# JTAG_-V06.net
KiCad netlist of a schematic drawn in Altium Designer
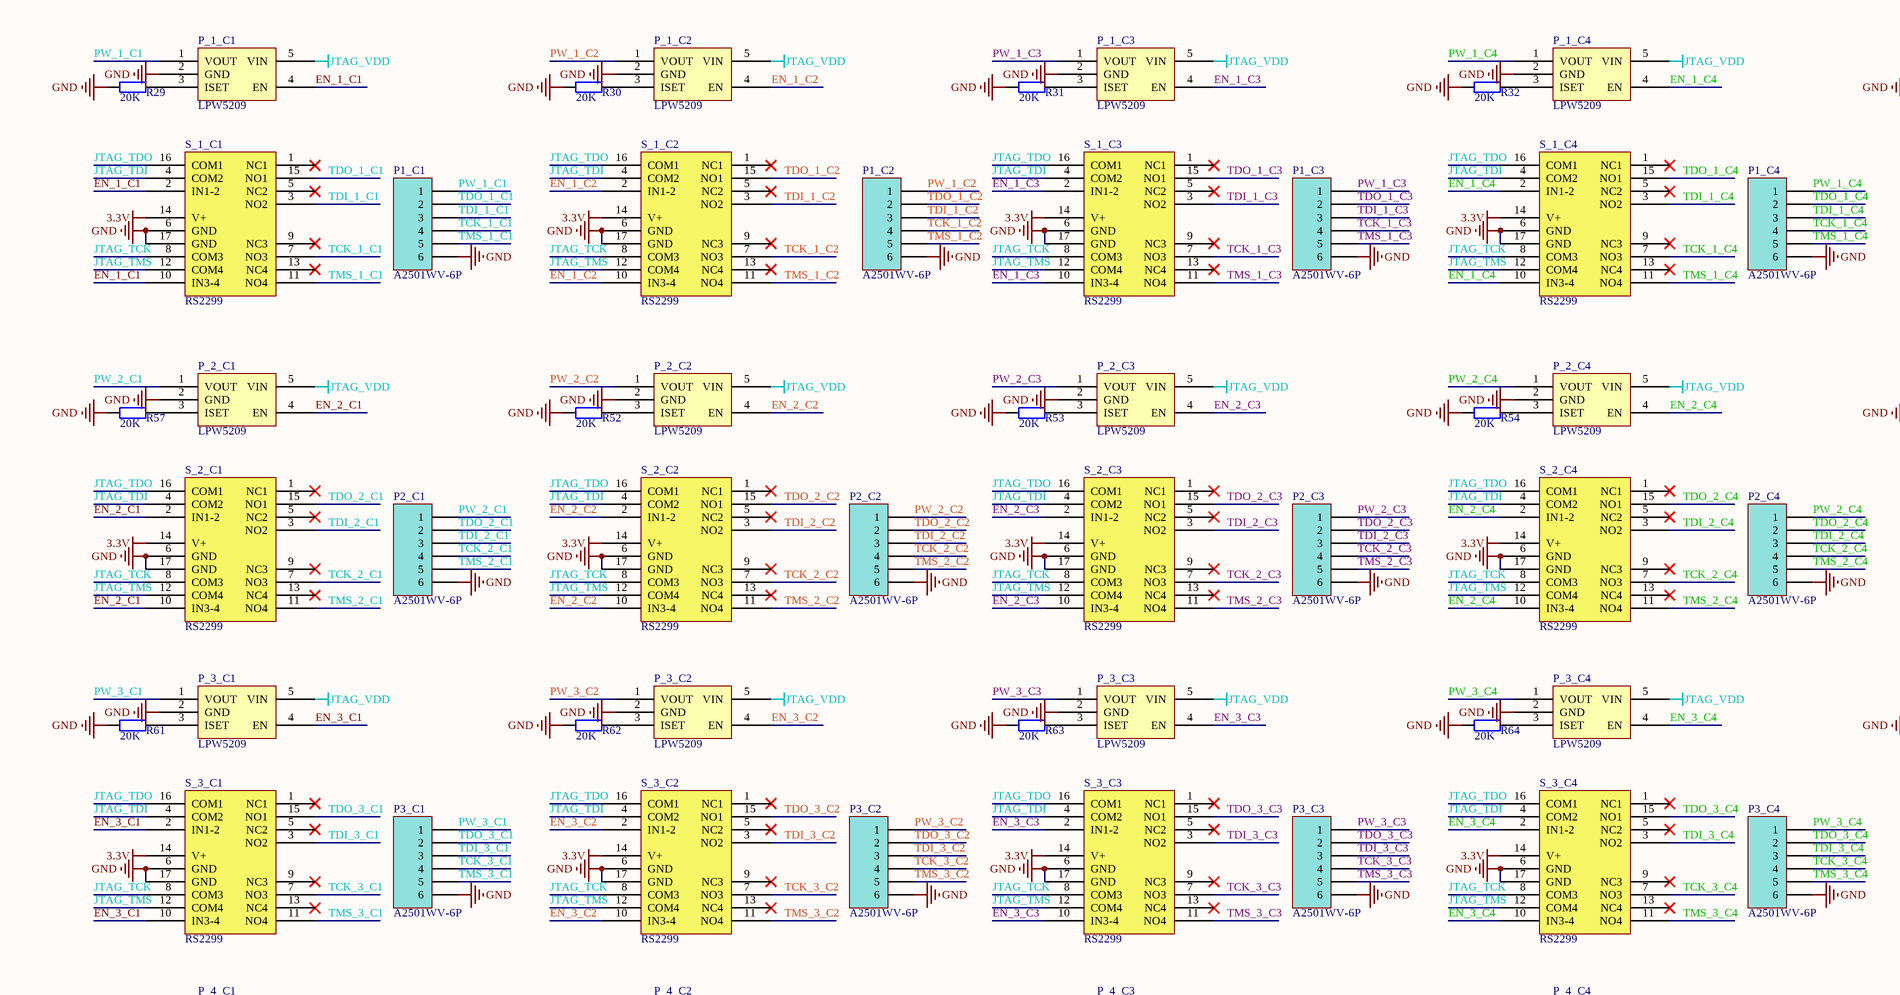
[diagram p0: JTAG批量下载板-V06.SchDoc, top left]
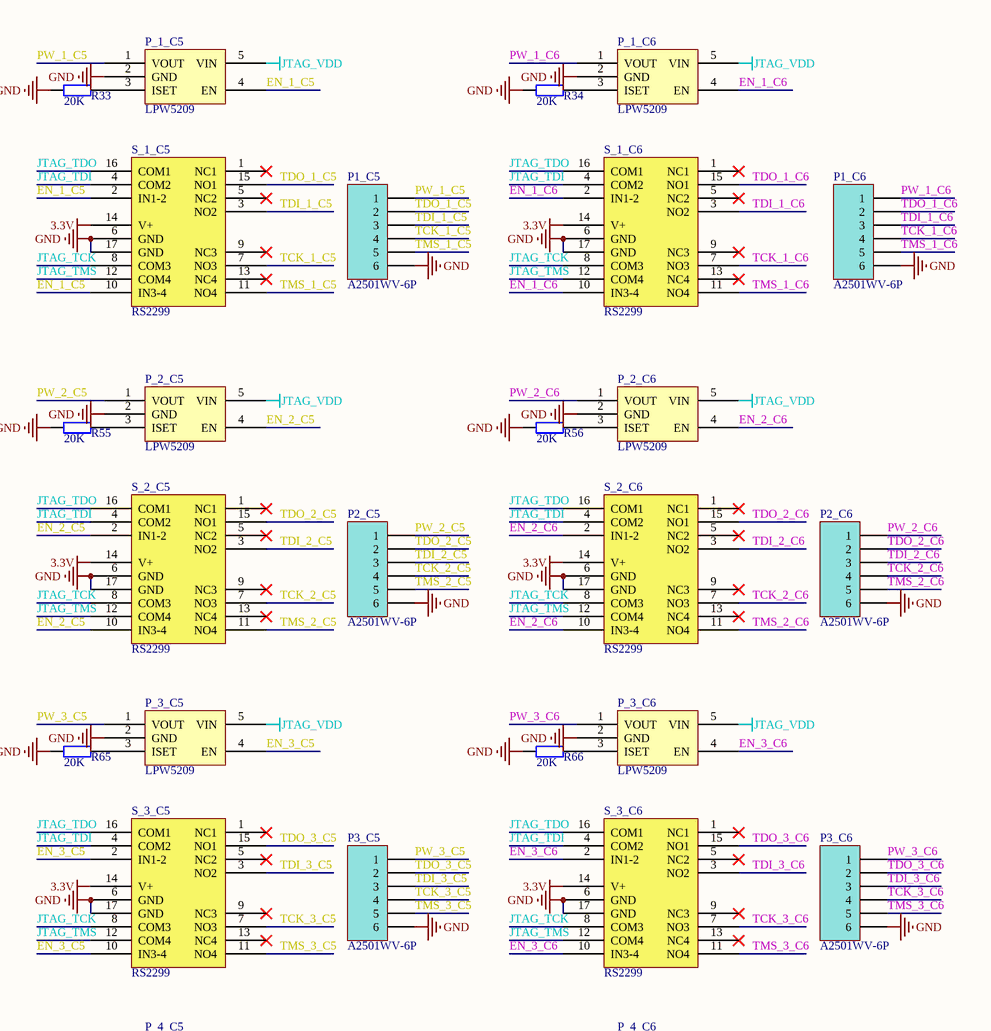
[diagram p1: JTAG批量下载板-V06.SchDoc, top right]
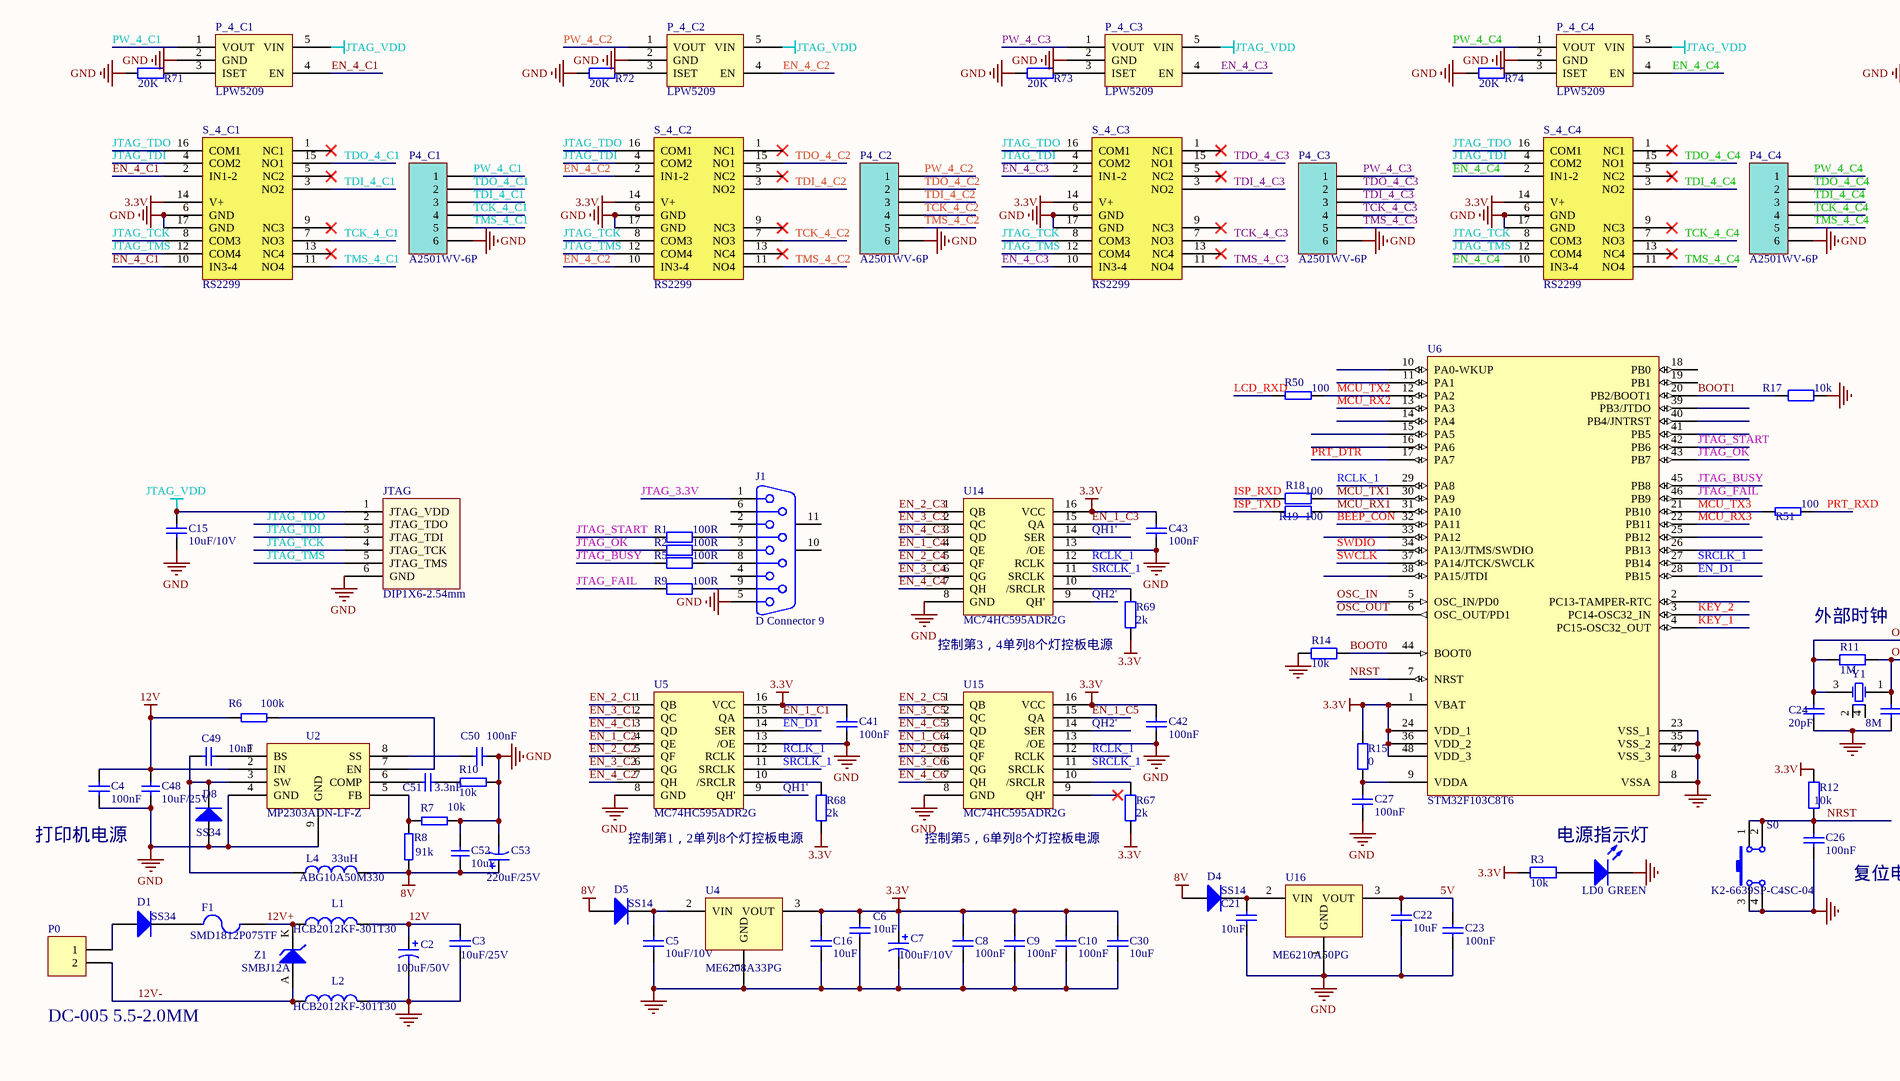
[diagram p2: JTAG批量下载板-V06.SchDoc, bottom left]
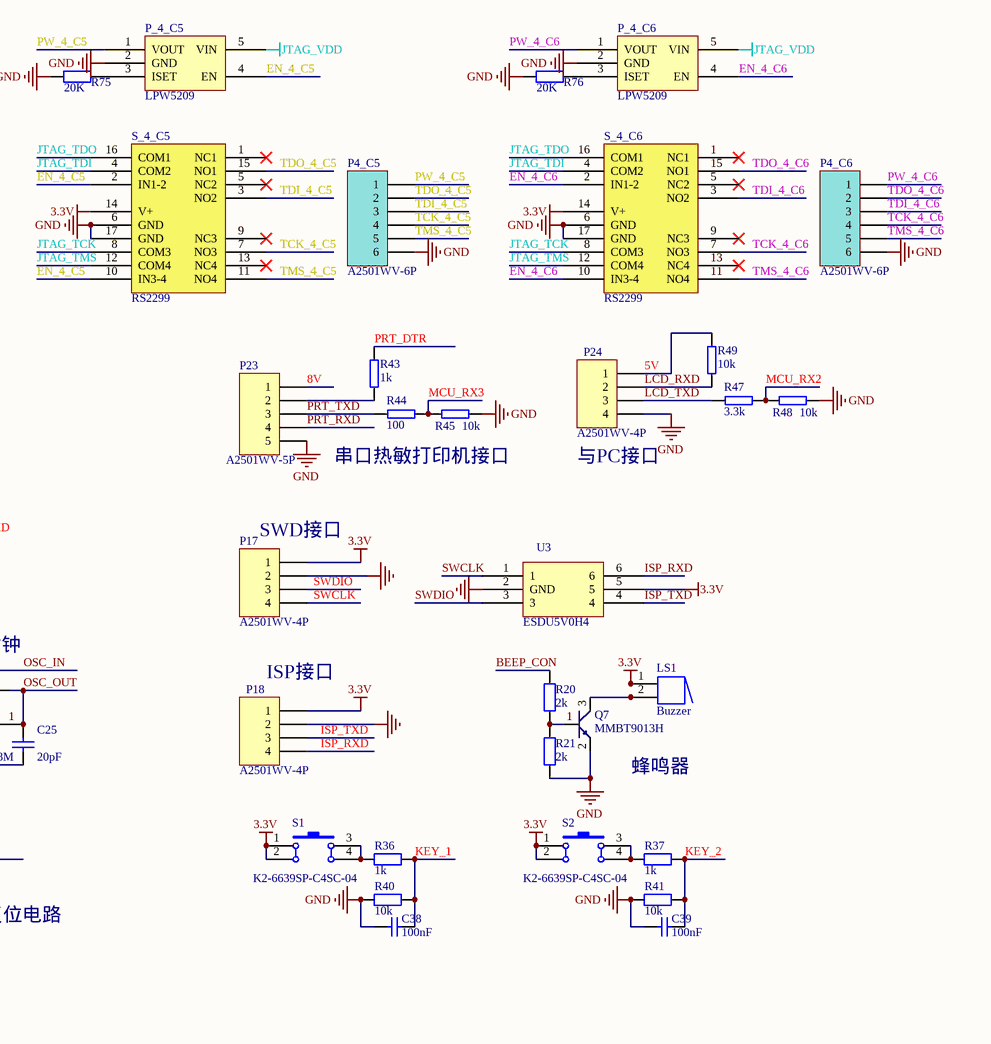
[diagram p3: JTAG批量下载板-V06.SchDoc, bottom right]

(export (version "E")
  (design (tool "Eeschema 10.0.6"))
  (components
    (comp (ref "C2")
      (value "100uF/50V")
      (footprint "RB-6*9")
      (description "Polarized Capacitor (Radial)")
      (fields (field (name "PUBLISHER") "Altium Limited"))
      (libsource (lib "Miscellaneous Devices") (part "Cap Pol1"))
    )
    (comp (ref "C3")
      (value "10uF/25V")
      (footprint "C0805")
      (description "Capacitor")
      (fields (field (name "PUBLISHER") "Altium Limited"))
      (libsource (lib "Miscellaneous Devices") (part "Cap"))
    )
    (comp (ref "C4")
      (value "100nF")
      (footprint "C0603")
      (description "Capacitor")
      (fields (field (name "PUBLISHER") "Altium Limited"))
      (libsource (lib "Miscellaneous Devices") (part "Cap"))
    )
    (comp (ref "C5")
      (value "10uF/10V")
      (footprint "C0603")
      (description "Capacitor")
      (fields (field (name "PUBLISHER") "Altium Limited"))
      (libsource (lib "Miscellaneous Devices") (part "Cap"))
    )
    (comp (ref "C6")
      (value "10uF")
      (footprint "C0603")
      (description "Capacitor")
      (fields (field (name "PUBLISHER") "Altium Limited"))
      (libsource (lib "Miscellaneous Devices") (part "Cap"))
    )
    (comp (ref "C7")
      (value "100uF/10V")
      (footprint "C3528")
      (description "Polarized Capacitor (Radial)")
      (fields (field (name "PUBLISHER") "Altium Limited"))
      (libsource (lib "Miscellaneous Devices") (part "Cap Pol1"))
    )
    (comp (ref "C8")
      (value "100nF")
      (footprint "C0603")
      (description "Capacitor")
      (fields (field (name "PUBLISHER") "Altium Limited"))
      (libsource (lib "Miscellaneous Devices") (part "Cap"))
    )
    (comp (ref "C9")
      (value "100nF")
      (footprint "C0603")
      (description "Capacitor")
      (fields (field (name "PUBLISHER") "Altium Limited"))
      (libsource (lib "Miscellaneous Devices") (part "Cap"))
    )
    (comp (ref "C10")
      (value "100nF")
      (footprint "C0603")
      (description "Capacitor")
      (fields (field (name "PUBLISHER") "Altium Limited"))
      (libsource (lib "Miscellaneous Devices") (part "Cap"))
    )
    (comp (ref "C15")
      (value "10uF/10V")
      (footprint "C0603")
      (description "Capacitor")
      (fields (field (name "PUBLISHER") "Altium Limited"))
      (libsource (lib "Miscellaneous Devices") (part "Cap"))
    )
    (comp (ref "C16")
      (value "10uF")
      (footprint "C0603")
      (description "Capacitor")
      (fields (field (name "PUBLISHER") "Altium Limited"))
      (libsource (lib "Miscellaneous Devices") (part "Cap"))
    )
    (comp (ref "C21")
      (value "10uF")
      (footprint "C0603")
      (description "Capacitor")
      (fields (field (name "PUBLISHER") "Altium Limited"))
      (libsource (lib "Miscellaneous Devices") (part "Cap"))
    )
    (comp (ref "C22")
      (value "10uF")
      (footprint "C0603")
      (description "Capacitor")
      (fields (field (name "PUBLISHER") "Altium Limited"))
      (libsource (lib "Miscellaneous Devices") (part "Cap"))
    )
    (comp (ref "C23")
      (value "100nF")
      (footprint "C0603")
      (description "Capacitor")
      (fields (field (name "PUBLISHER") "Altium Limited"))
      (libsource (lib "Miscellaneous Devices") (part "Cap"))
    )
    (comp (ref "C24")
      (value "20pF")
      (footprint "C0603")
      (description "Capacitor")
      (fields (field (name "PUBLISHER") "Altium Limited"))
      (libsource (lib "Miscellaneous Devices") (part "Cap"))
    )
    (comp (ref "C25")
      (value "20pF")
      (footprint "C0603")
      (description "Capacitor")
      (fields (field (name "PUBLISHER") "Altium Limited"))
      (libsource (lib "Miscellaneous Devices") (part "Cap"))
    )
    (comp (ref "C26")
      (value "100nF")
      (footprint "C0603")
      (description "Capacitor")
      (fields (field (name "PUBLISHER") "Altium Limited"))
      (libsource (lib "Miscellaneous Devices") (part "Cap"))
    )
    (comp (ref "C27")
      (value "100nF")
      (footprint "C0603")
      (description "Capacitor")
      (fields (field (name "PUBLISHER") "Altium Limited"))
      (libsource (lib "Miscellaneous Devices") (part "Cap"))
    )
    (comp (ref "C30")
      (value "10uF")
      (footprint "C0603")
      (description "Capacitor")
      (fields (field (name "PUBLISHER") "Altium Limited"))
      (libsource (lib "Miscellaneous Devices") (part "Cap"))
    )
    (comp (ref "C38")
      (value "100nF")
      (footprint "C0603")
      (description "电容器")
      (libsource (lib "*") (part "Capacitor"))
    )
    (comp (ref "C39")
      (value "100nF")
      (footprint "C0603")
      (description "电容器")
      (libsource (lib "*") (part "Capacitor"))
    )
    (comp (ref "C41")
      (value "100nF")
      (footprint "C0603")
      (description "Capacitor")
      (fields (field (name "PUBLISHER") "Altium Limited"))
      (libsource (lib "Miscellaneous Devices") (part "Cap"))
    )
    (comp (ref "C42")
      (value "100nF")
      (footprint "C0603")
      (description "Capacitor")
      (fields (field (name "PUBLISHER") "Altium Limited"))
      (libsource (lib "Miscellaneous Devices") (part "Cap"))
    )
    (comp (ref "C43")
      (value "100nF")
      (footprint "C0603")
      (description "Capacitor")
      (fields (field (name "PUBLISHER") "Altium Limited"))
      (libsource (lib "Miscellaneous Devices") (part "Cap"))
    )
    (comp (ref "C48")
      (value "10uF/25V")
      (footprint "C0805")
      (description "电容器")
      (libsource (lib "*") (part "Capacitor"))
    )
    (comp (ref "C49")
      (value "10nF")
      (footprint "C0603")
      (description "电容器")
      (libsource (lib "*") (part "Capacitor"))
    )
    (comp (ref "C50")
      (value "100nF")
      (footprint "C0603")
      (description "电容器")
      (libsource (lib "*") (part "Capacitor"))
    )
    (comp (ref "C51")
      (value "3.3nF")
      (footprint "C0603")
      (description "电容器")
      (libsource (lib "*") (part "Capacitor"))
    )
    (comp (ref "C52")
      (value "10uF")
      (footprint "C0603")
      (description "电容器")
      (libsource (lib "*") (part "Capacitor"))
    )
    (comp (ref "C53")
      (value "220uF/25V")
      (footprint "RB-6*9")
      (description "Polarized Capacitor (Radial)")
      (fields (field (name "PUBLISHER") "Altium Limited"))
      (libsource (lib "Miscellaneous Devices") (part "Cap Pol1"))
    )
    (comp (ref "D1")
      (value "SS34")
      (footprint "SMB")
      (description "1 Amp General Purpose Rectifier")
      (fields (field (name "PUBLISHER") "Altium Limited"))
      (libsource (lib "Miscellaneous Devices") (part "Diode 1N4001"))
    )
    (comp (ref "D4")
      (value "SS14")
      (footprint "SOD-123F")
      (description "1 Amp General Purpose Rectifier")
      (fields (field (name "PUBLISHER") "Altium Limited"))
      (libsource (lib "Miscellaneous Devices") (part "Diode 1N4001"))
    )
    (comp (ref "D5")
      (value "SS14")
      (footprint "SOD-123F")
      (description "1 Amp General Purpose Rectifier")
      (fields (field (name "PUBLISHER") "Altium Limited"))
      (libsource (lib "Miscellaneous Devices") (part "Diode 1N4001"))
    )
    (comp (ref "D8")
      (value "SS34")
      (footprint "SMB")
      (description "通用二极管")
      (fields (field (name "PUBLISHER") "Altium Limited"))
      (libsource (lib "*") (part "Diode"))
    )
    (comp (ref "F1")
      (value "SMD1812P075TF")
      (footprint "1812")
      (description "Fuse")
      (fields (field (name "PUBLISHER") "Altium Limited"))
      (libsource (lib "Miscellaneous Devices") (part "Fuse 2"))
    )
    (comp (ref "J1")
      (value "D Connector 9")
      (footprint "DSUB1.385-2H9")
      (description "Receptacle Assembly, 9 Position, Right Angle")
      (fields (field (name "PUBLISHER") "Altium Limited"))
      (libsource (lib "Miscellaneous Connectors") (part "D Connector 9"))
    )
    (comp (ref "JTAG")
      (value "DIP1X6-2.54mm")
      (footprint "XH2.5-6P")
      (libsource (lib "JTAG批量下载板-V0.1") (part "DIP1X6-2.54mm"))
    )
    (comp (ref "L1")
      (value "HCB2012KF-301T30")
      (footprint "R0805")
      (description "Inductor")
      (fields (field (name "PUBLISHER") "Altium Limited"))
      (libsource (lib "Miscellaneous Devices") (part "Inductor"))
    )
    (comp (ref "L2")
      (value "HCB2012KF-301T30")
      (footprint "R0805")
      (description "Inductor")
      (fields (field (name "PUBLISHER") "Altium Limited"))
      (libsource (lib "Miscellaneous Devices") (part "Inductor"))
    )
    (comp (ref "L4")
      (value "33uH")
      (footprint "L1040")
      (description "Inductor")
      (fields (field (name "ALTIUM_VALUE") "ABG10A50M330") (field (name "PUBLISHER") "Altium Limited"))
      (libsource (lib "") (part "Inductor_1"))
    )
    (comp (ref "LD0")
      (value "GREEN")
      (footprint "LED-0603")
      (description "LED灯")
      (fields (field (name "PUBLISHER") "Altium Limited"))
      (libsource (lib "*") (part "LED0"))
    )
    (comp (ref "LS1")
      (value "Buzzer")
      (footprint "BUZZER-small")
      (description "Magnetic Transducer Buzzer")
      (fields (field (name "PUBLISHER") "Altium Limited"))
      (libsource (lib "JTAG-1") (part "Buzzer"))
    )
    (comp (ref "P0")
      (value "DC-005 5.5-2.0MM")
      (footprint "DC-005A")
      (description "Header, 2-Pin")
      (fields (field (name "PUBLISHER") "Altium Limited"))
      (libsource (lib "Miscellaneous Connectors") (part "Header 2"))
    )
    (comp (ref "P1_C1")
      (value "A2501WV-6P")
      (footprint "XH2.5-6P")
      (description "Header, 6-Pin")
      (fields (field (name "PUBLISHER") "Altium Limited"))
      (libsource (lib "JTAG批量下载板-V0.2") (part "Header 6"))
    )
    (comp (ref "P1_C2")
      (value "A2501WV-6P")
      (footprint "XH2.5-6P")
      (description "Header, 6-Pin")
      (fields (field (name "PUBLISHER") "Altium Limited"))
      (libsource (lib "JTAG批量下载板-V0.2") (part "Header 6"))
    )
    (comp (ref "P1_C3")
      (value "A2501WV-6P")
      (footprint "XH2.5-6P")
      (description "Header, 6-Pin")
      (fields (field (name "PUBLISHER") "Altium Limited"))
      (libsource (lib "JTAG批量下载板-V0.2") (part "Header 6"))
    )
    (comp (ref "P1_C4")
      (value "A2501WV-6P")
      (footprint "XH2.5-6P")
      (description "Header, 6-Pin")
      (fields (field (name "PUBLISHER") "Altium Limited"))
      (libsource (lib "JTAG批量下载板-V0.2") (part "Header 6"))
    )
    (comp (ref "P1_C5")
      (value "A2501WV-6P")
      (footprint "XH2.5-6P")
      (description "Header, 6-Pin")
      (fields (field (name "PUBLISHER") "Altium Limited"))
      (libsource (lib "JTAG批量下载板-V0.2") (part "Header 6"))
    )
    (comp (ref "P1_C6")
      (value "A2501WV-6P")
      (footprint "XH2.5-6P")
      (description "Header, 6-Pin")
      (fields (field (name "PUBLISHER") "Altium Limited"))
      (libsource (lib "JTAG批量下载板-V0.2") (part "Header 6"))
    )
    (comp (ref "P2_C1")
      (value "A2501WV-6P")
      (footprint "XH2.5-6P")
      (description "Header, 6-Pin")
      (fields (field (name "PUBLISHER") "Altium Limited"))
      (libsource (lib "JTAG批量下载板-V0.2") (part "Header 6"))
    )
    (comp (ref "P2_C2")
      (value "A2501WV-6P")
      (footprint "XH2.5-6P")
      (description "Header, 6-Pin")
      (fields (field (name "PUBLISHER") "Altium Limited"))
      (libsource (lib "JTAG批量下载板-V0.2") (part "Header 6"))
    )
    (comp (ref "P2_C3")
      (value "A2501WV-6P")
      (footprint "XH2.5-6P")
      (description "Header, 6-Pin")
      (fields (field (name "PUBLISHER") "Altium Limited"))
      (libsource (lib "JTAG批量下载板-V0.2") (part "Header 6"))
    )
    (comp (ref "P2_C4")
      (value "A2501WV-6P")
      (footprint "XH2.5-6P")
      (description "Header, 6-Pin")
      (fields (field (name "PUBLISHER") "Altium Limited"))
      (libsource (lib "JTAG批量下载板-V0.2") (part "Header 6"))
    )
    (comp (ref "P2_C5")
      (value "A2501WV-6P")
      (footprint "XH2.5-6P")
      (description "Header, 6-Pin")
      (fields (field (name "PUBLISHER") "Altium Limited"))
      (libsource (lib "JTAG批量下载板-V0.2") (part "Header 6"))
    )
    (comp (ref "P2_C6")
      (value "A2501WV-6P")
      (footprint "XH2.5-6P")
      (description "Header, 6-Pin")
      (fields (field (name "PUBLISHER") "Altium Limited"))
      (libsource (lib "JTAG批量下载板-V0.2") (part "Header 6"))
    )
    (comp (ref "P3_C1")
      (value "A2501WV-6P")
      (footprint "XH2.5-6P")
      (description "Header, 6-Pin")
      (fields (field (name "PUBLISHER") "Altium Limited"))
      (libsource (lib "JTAG批量下载板-V0.2") (part "Header 6"))
    )
    (comp (ref "P3_C2")
      (value "A2501WV-6P")
      (footprint "XH2.5-6P")
      (description "Header, 6-Pin")
      (fields (field (name "PUBLISHER") "Altium Limited"))
      (libsource (lib "JTAG批量下载板-V0.2") (part "Header 6"))
    )
    (comp (ref "P3_C3")
      (value "A2501WV-6P")
      (footprint "XH2.5-6P")
      (description "Header, 6-Pin")
      (fields (field (name "PUBLISHER") "Altium Limited"))
      (libsource (lib "JTAG批量下载板-V0.2") (part "Header 6"))
    )
    (comp (ref "P3_C4")
      (value "A2501WV-6P")
      (footprint "XH2.5-6P")
      (description "Header, 6-Pin")
      (fields (field (name "PUBLISHER") "Altium Limited"))
      (libsource (lib "JTAG批量下载板-V0.2") (part "Header 6"))
    )
    (comp (ref "P3_C5")
      (value "A2501WV-6P")
      (footprint "XH2.5-6P")
      (description "Header, 6-Pin")
      (fields (field (name "PUBLISHER") "Altium Limited"))
      (libsource (lib "JTAG批量下载板-V0.2") (part "Header 6"))
    )
    (comp (ref "P3_C6")
      (value "A2501WV-6P")
      (footprint "XH2.5-6P")
      (description "Header, 6-Pin")
      (fields (field (name "PUBLISHER") "Altium Limited"))
      (libsource (lib "JTAG批量下载板-V0.2") (part "Header 6"))
    )
    (comp (ref "P4_C1")
      (value "A2501WV-6P")
      (footprint "XH2.5-6P")
      (description "Header, 6-Pin")
      (fields (field (name "PUBLISHER") "Altium Limited"))
      (libsource (lib "JTAG批量下载板-V0.2") (part "Header 6"))
    )
    (comp (ref "P4_C2")
      (value "A2501WV-6P")
      (footprint "XH2.5-6P")
      (description "Header, 6-Pin")
      (fields (field (name "PUBLISHER") "Altium Limited"))
      (libsource (lib "JTAG批量下载板-V0.2") (part "Header 6"))
    )
    (comp (ref "P4_C3")
      (value "A2501WV-6P")
      (footprint "XH2.5-6P")
      (description "Header, 6-Pin")
      (fields (field (name "PUBLISHER") "Altium Limited"))
      (libsource (lib "JTAG批量下载板-V0.2") (part "Header 6"))
    )
    (comp (ref "P4_C4")
      (value "A2501WV-6P")
      (footprint "XH2.5-6P")
      (description "Header, 6-Pin")
      (fields (field (name "PUBLISHER") "Altium Limited"))
      (libsource (lib "JTAG批量下载板-V0.2") (part "Header 6"))
    )
    (comp (ref "P4_C5")
      (value "A2501WV-6P")
      (footprint "XH2.5-6P")
      (description "Header, 6-Pin")
      (fields (field (name "PUBLISHER") "Altium Limited"))
      (libsource (lib "JTAG批量下载板-V0.2") (part "Header 6"))
    )
    (comp (ref "P4_C6")
      (value "A2501WV-6P")
      (footprint "XH2.5-6P")
      (description "Header, 6-Pin")
      (fields (field (name "PUBLISHER") "Altium Limited"))
      (libsource (lib "JTAG批量下载板-V0.2") (part "Header 6"))
    )
    (comp (ref "P17")
      (value "A2501WV-4P")
      (footprint "XH2.5-4P")
      (description "Header, 4-Pin")
      (fields (field (name "PUBLISHER") "Altium Limited"))
      (libsource (lib "*") (part "Header 4"))
    )
    (comp (ref "P18")
      (value "A2501WV-4P")
      (footprint "XH2.5-4P")
      (description "Header, 4-Pin")
      (fields (field (name "PUBLISHER") "Altium Limited"))
      (libsource (lib "*") (part "Header 4"))
    )
    (comp (ref "P23")
      (value "A2501WV-5P")
      (footprint "XH2.5-5P")
      (description "Header, 5-Pin")
      (fields (field (name "PUBLISHER") "Altium Limited"))
      (libsource (lib "Miscellaneous Connectors") (part "Header 5"))
    )
    (comp (ref "P24")
      (value "A2501WV-4P")
      (footprint "XH2.5-4P")
      (description "Header, 4-Pin")
      (fields (field (name "PUBLISHER") "Altium Limited"))
      (libsource (lib "*") (part "Header 4"))
    )
    (comp (ref "P_1_C1")
      (value "LPW5209")
      (footprint "SOT-23-5")
      (libsource (lib "JTAG批量下载板-V0.1") (part "LPW5209"))
    )
    (comp (ref "P_1_C2")
      (value "LPW5209")
      (footprint "SOT-23-5")
      (libsource (lib "JTAG批量下载板-V0.1") (part "LPW5209"))
    )
    (comp (ref "P_1_C3")
      (value "LPW5209")
      (footprint "SOT-23-5")
      (libsource (lib "JTAG批量下载板-V0.1") (part "LPW5209"))
    )
    (comp (ref "P_1_C4")
      (value "LPW5209")
      (footprint "SOT-23-5")
      (libsource (lib "JTAG批量下载板-V0.1") (part "LPW5209"))
    )
    (comp (ref "P_1_C5")
      (value "LPW5209")
      (footprint "SOT-23-5")
      (libsource (lib "JTAG批量下载板-V0.1") (part "LPW5209"))
    )
    (comp (ref "P_1_C6")
      (value "LPW5209")
      (footprint "SOT-23-5")
      (libsource (lib "JTAG批量下载板-V0.1") (part "LPW5209"))
    )
    (comp (ref "P_2_C1")
      (value "LPW5209")
      (footprint "SOT-23-5")
      (libsource (lib "JTAG批量下载板-V0.1") (part "LPW5209"))
    )
    (comp (ref "P_2_C2")
      (value "LPW5209")
      (footprint "SOT-23-5")
      (libsource (lib "JTAG批量下载板-V0.1") (part "LPW5209"))
    )
    (comp (ref "P_2_C3")
      (value "LPW5209")
      (footprint "SOT-23-5")
      (libsource (lib "JTAG批量下载板-V0.1") (part "LPW5209"))
    )
    (comp (ref "P_2_C4")
      (value "LPW5209")
      (footprint "SOT-23-5")
      (libsource (lib "JTAG批量下载板-V0.1") (part "LPW5209"))
    )
    (comp (ref "P_2_C5")
      (value "LPW5209")
      (footprint "SOT-23-5")
      (libsource (lib "JTAG批量下载板-V0.1") (part "LPW5209"))
    )
    (comp (ref "P_2_C6")
      (value "LPW5209")
      (footprint "SOT-23-5")
      (libsource (lib "JTAG批量下载板-V0.1") (part "LPW5209"))
    )
    (comp (ref "P_3_C1")
      (value "LPW5209")
      (footprint "SOT-23-5")
      (libsource (lib "JTAG批量下载板-V0.1") (part "LPW5209"))
    )
    (comp (ref "P_3_C2")
      (value "LPW5209")
      (footprint "SOT-23-5")
      (libsource (lib "JTAG批量下载板-V0.1") (part "LPW5209"))
    )
    (comp (ref "P_3_C3")
      (value "LPW5209")
      (footprint "SOT-23-5")
      (libsource (lib "JTAG批量下载板-V0.1") (part "LPW5209"))
    )
    (comp (ref "P_3_C4")
      (value "LPW5209")
      (footprint "SOT-23-5")
      (libsource (lib "JTAG批量下载板-V0.1") (part "LPW5209"))
    )
    (comp (ref "P_3_C5")
      (value "LPW5209")
      (footprint "SOT-23-5")
      (libsource (lib "JTAG批量下载板-V0.1") (part "LPW5209"))
    )
    (comp (ref "P_3_C6")
      (value "LPW5209")
      (footprint "SOT-23-5")
      (libsource (lib "JTAG批量下载板-V0.1") (part "LPW5209"))
    )
    (comp (ref "P_4_C1")
      (value "LPW5209")
      (footprint "SOT-23-5")
      (libsource (lib "JTAG批量下载板-V0.1") (part "LPW5209"))
    )
    (comp (ref "P_4_C2")
      (value "LPW5209")
      (footprint "SOT-23-5")
      (libsource (lib "JTAG批量下载板-V0.1") (part "LPW5209"))
    )
    (comp (ref "P_4_C3")
      (value "LPW5209")
      (footprint "SOT-23-5")
      (libsource (lib "JTAG批量下载板-V0.1") (part "LPW5209"))
    )
    (comp (ref "P_4_C4")
      (value "LPW5209")
      (footprint "SOT-23-5")
      (libsource (lib "JTAG批量下载板-V0.1") (part "LPW5209"))
    )
    (comp (ref "P_4_C5")
      (value "LPW5209")
      (footprint "SOT-23-5")
      (libsource (lib "JTAG批量下载板-V0.1") (part "LPW5209"))
    )
    (comp (ref "P_4_C6")
      (value "LPW5209")
      (footprint "SOT-23-5")
      (libsource (lib "JTAG批量下载板-V0.1") (part "LPW5209"))
    )
    (comp (ref "Q7")
      (value "MMBT9013H")
      (footprint "SOT-23")
      (description "8050/BCW846/BCW847")
      (libsource (lib "MY_STD_SCH") (part "MY_NPN"))
    )
    (comp (ref "R1")
      (value "100R")
      (footprint "R0603")
      (description "Resistor")
      (fields (field (name "PUBLISHER") "Altium Limited"))
      (libsource (lib "Miscellaneous Devices") (part "Res2"))
    )
    (comp (ref "R2")
      (value "100R")
      (footprint "R0603")
      (description "Resistor")
      (fields (field (name "PUBLISHER") "Altium Limited"))
      (libsource (lib "Miscellaneous Devices") (part "Res2"))
    )
    (comp (ref "R3")
      (value "10k")
      (footprint "R0603")
      (description "Resistor")
      (fields (field (name "PUBLISHER") "Altium Limited"))
      (libsource (lib "") (part "Res2_1"))
    )
    (comp (ref "R5")
      (value "100R")
      (footprint "R0603")
      (description "Resistor")
      (fields (field (name "PUBLISHER") "Altium Limited"))
      (libsource (lib "Miscellaneous Devices") (part "Res2"))
    )
    (comp (ref "R6")
      (value "100k")
      (footprint "R0603")
      (description "电阻器")
      (libsource (lib "*") (part "Resistance"))
    )
    (comp (ref "R7")
      (value "10k")
      (footprint "R0603")
      (description "电阻器")
      (libsource (lib "*") (part "Resistance"))
    )
    (comp (ref "R8")
      (value "91k")
      (footprint "R0603")
      (description "电阻器")
      (libsource (lib "*") (part "Resistance"))
    )
    (comp (ref "R9")
      (value "100R")
      (footprint "R0603")
      (description "Resistor")
      (fields (field (name "PUBLISHER") "Altium Limited"))
      (libsource (lib "Miscellaneous Devices") (part "Res2"))
    )
    (comp (ref "R10")
      (value "10k")
      (footprint "R0603")
      (description "电阻器")
      (libsource (lib "*") (part "Resistance"))
    )
    (comp (ref "R11")
      (value "1M")
      (footprint "R0603")
      (description "Resistor")
      (fields (field (name "PUBLISHER") "Altium Limited"))
      (libsource (lib "") (part "Res2_1"))
    )
    (comp (ref "R12")
      (value "10k")
      (footprint "R0603")
      (description "Resistor")
      (fields (field (name "PUBLISHER") "Altium Limited"))
      (libsource (lib "") (part "Res2_2"))
    )
    (comp (ref "R14")
      (value "10k")
      (footprint "R0603")
      (description "Resistor")
      (fields (field (name "PUBLISHER") "Altium Limited"))
      (libsource (lib "") (part "Res2_1"))
    )
    (comp (ref "R15")
      (value "0")
      (footprint "R0603")
      (description "Resistor")
      (fields (field (name "PUBLISHER") "Altium Limited"))
      (libsource (lib "") (part "Res2_2"))
    )
    (comp (ref "R17")
      (value "10k")
      (footprint "R0603")
      (description "Resistor")
      (fields (field (name "PUBLISHER") "Altium Limited"))
      (libsource (lib "Miscellaneous Devices") (part "Res2"))
    )
    (comp (ref "R18")
      (value "100")
      (footprint "R0603")
      (description "Resistor")
      (fields (field (name "PUBLISHER") "Altium Limited"))
      (libsource (lib "") (part "Res2_1"))
    )
    (comp (ref "R19")
      (value "100")
      (footprint "R0603")
      (description "Resistor")
      (fields (field (name "PUBLISHER") "Altium Limited"))
      (libsource (lib "") (part "Res2_1"))
    )
    (comp (ref "R20")
      (value "2k")
      (footprint "R0603")
      (description "Resistor")
      (fields (field (name "PUBLISHER") "Altium Limited"))
      (libsource (lib "") (part "Res2_3"))
    )
    (comp (ref "R21")
      (value "2k")
      (footprint "R0603")
      (description "Resistor")
      (fields (field (name "PUBLISHER") "Altium Limited"))
      (libsource (lib "") (part "Res2_2"))
    )
    (comp (ref "R29")
      (value "20K")
      (footprint "R0603")
      (description "Resistor")
      (fields (field (name "PUBLISHER") "Altium Limited"))
      (libsource (lib "Miscellaneous Devices") (part "Res2"))
    )
    (comp (ref "R30")
      (value "20K")
      (footprint "R0603")
      (description "Resistor")
      (fields (field (name "PUBLISHER") "Altium Limited"))
      (libsource (lib "Miscellaneous Devices") (part "Res2"))
    )
    (comp (ref "R31")
      (value "20K")
      (footprint "R0603")
      (description "Resistor")
      (fields (field (name "PUBLISHER") "Altium Limited"))
      (libsource (lib "Miscellaneous Devices") (part "Res2"))
    )
    (comp (ref "R32")
      (value "20K")
      (footprint "R0603")
      (description "Resistor")
      (fields (field (name "PUBLISHER") "Altium Limited"))
      (libsource (lib "Miscellaneous Devices") (part "Res2"))
    )
    (comp (ref "R33")
      (value "20K")
      (footprint "R0603")
      (description "Resistor")
      (fields (field (name "PUBLISHER") "Altium Limited"))
      (libsource (lib "Miscellaneous Devices") (part "Res2"))
    )
    (comp (ref "R34")
      (value "20K")
      (footprint "R0603")
      (description "Resistor")
      (fields (field (name "PUBLISHER") "Altium Limited"))
      (libsource (lib "Miscellaneous Devices") (part "Res2"))
    )
    (comp (ref "R36")
      (value "1k")
      (footprint "R0603")
      (description "Resistor")
      (fields (field (name "PUBLISHER") "Altium Limited"))
      (libsource (lib "Miscellaneous Devices") (part "Res2"))
    )
    (comp (ref "R37")
      (value "1k")
      (footprint "R0603")
      (description "Resistor")
      (fields (field (name "PUBLISHER") "Altium Limited"))
      (libsource (lib "Miscellaneous Devices") (part "Res2"))
    )
    (comp (ref "R40")
      (value "10k")
      (footprint "R0603")
      (description "Resistor")
      (fields (field (name "PUBLISHER") "Altium Limited"))
      (libsource (lib "Miscellaneous Devices") (part "Res2"))
    )
    (comp (ref "R41")
      (value "10k")
      (footprint "R0603")
      (description "Resistor")
      (fields (field (name "PUBLISHER") "Altium Limited"))
      (libsource (lib "Miscellaneous Devices") (part "Res2"))
    )
    (comp (ref "R43")
      (value "1k")
      (footprint "R0603")
      (description "电阻器")
      (libsource (lib "*") (part "Resistance"))
    )
    (comp (ref "R44")
      (value "100")
      (footprint "R0603")
      (description "电阻器")
      (libsource (lib "*") (part "Resistance"))
    )
    (comp (ref "R45")
      (value "10k")
      (footprint "R0603")
      (description "电阻器")
      (libsource (lib "*") (part "Resistance"))
    )
    (comp (ref "R47")
      (value "3.3k")
      (footprint "R0603")
      (description "电阻器")
      (libsource (lib "*") (part "Resistance"))
    )
    (comp (ref "R48")
      (value "10k")
      (footprint "R0603")
      (description "电阻器")
      (libsource (lib "*") (part "Resistance"))
    )
    (comp (ref "R49")
      (value "10k")
      (footprint "R0603")
      (description "电阻器")
      (libsource (lib "*") (part "Resistance"))
    )
    (comp (ref "R50")
      (value "100")
      (footprint "R0603")
      (description "电阻器")
      (libsource (lib "*") (part "Resistance"))
    )
    (comp (ref "R51")
      (value "100")
      (footprint "R0603")
      (description "电阻器")
      (libsource (lib "*") (part "Resistance"))
    )
    (comp (ref "R52")
      (value "20K")
      (footprint "R0603")
      (description "Resistor")
      (fields (field (name "PUBLISHER") "Altium Limited"))
      (libsource (lib "Miscellaneous Devices") (part "Res2"))
    )
    (comp (ref "R53")
      (value "20K")
      (footprint "R0603")
      (description "Resistor")
      (fields (field (name "PUBLISHER") "Altium Limited"))
      (libsource (lib "Miscellaneous Devices") (part "Res2"))
    )
    (comp (ref "R54")
      (value "20K")
      (footprint "R0603")
      (description "Resistor")
      (fields (field (name "PUBLISHER") "Altium Limited"))
      (libsource (lib "Miscellaneous Devices") (part "Res2"))
    )
    (comp (ref "R55")
      (value "20K")
      (footprint "R0603")
      (description "Resistor")
      (fields (field (name "PUBLISHER") "Altium Limited"))
      (libsource (lib "Miscellaneous Devices") (part "Res2"))
    )
    (comp (ref "R56")
      (value "20K")
      (footprint "R0603")
      (description "Resistor")
      (fields (field (name "PUBLISHER") "Altium Limited"))
      (libsource (lib "Miscellaneous Devices") (part "Res2"))
    )
    (comp (ref "R57")
      (value "20K")
      (footprint "R0603")
      (description "Resistor")
      (fields (field (name "PUBLISHER") "Altium Limited"))
      (libsource (lib "Miscellaneous Devices") (part "Res2"))
    )
    (comp (ref "R61")
      (value "20K")
      (footprint "R0603")
      (description "Resistor")
      (fields (field (name "PUBLISHER") "Altium Limited"))
      (libsource (lib "Miscellaneous Devices") (part "Res2"))
    )
    (comp (ref "R62")
      (value "20K")
      (footprint "R0603")
      (description "Resistor")
      (fields (field (name "PUBLISHER") "Altium Limited"))
      (libsource (lib "Miscellaneous Devices") (part "Res2"))
    )
    (comp (ref "R63")
      (value "20K")
      (footprint "R0603")
      (description "Resistor")
      (fields (field (name "PUBLISHER") "Altium Limited"))
      (libsource (lib "Miscellaneous Devices") (part "Res2"))
    )
    (comp (ref "R64")
      (value "20K")
      (footprint "R0603")
      (description "Resistor")
      (fields (field (name "PUBLISHER") "Altium Limited"))
      (libsource (lib "Miscellaneous Devices") (part "Res2"))
    )
    (comp (ref "R65")
      (value "20K")
      (footprint "R0603")
      (description "Resistor")
      (fields (field (name "PUBLISHER") "Altium Limited"))
      (libsource (lib "Miscellaneous Devices") (part "Res2"))
    )
    (comp (ref "R66")
      (value "20K")
      (footprint "R0603")
      (description "Resistor")
      (fields (field (name "PUBLISHER") "Altium Limited"))
      (libsource (lib "Miscellaneous Devices") (part "Res2"))
    )
    (comp (ref "R67")
      (value "2k")
      (footprint "R0603")
      (description "Resistor")
      (fields (field (name "PUBLISHER") "Altium Limited"))
      (libsource (lib "") (part "Res2_2"))
    )
    (comp (ref "R68")
      (value "2k")
      (footprint "R0603")
      (description "Resistor")
      (fields (field (name "PUBLISHER") "Altium Limited"))
      (libsource (lib "") (part "Res2_2"))
    )
    (comp (ref "R69")
      (value "2k")
      (footprint "R0603")
      (description "Resistor")
      (fields (field (name "PUBLISHER") "Altium Limited"))
      (libsource (lib "") (part "Res2_2"))
    )
    (comp (ref "R71")
      (value "20K")
      (footprint "R0603")
      (description "Resistor")
      (fields (field (name "PUBLISHER") "Altium Limited"))
      (libsource (lib "Miscellaneous Devices") (part "Res2"))
    )
    (comp (ref "R72")
      (value "20K")
      (footprint "R0603")
      (description "Resistor")
      (fields (field (name "PUBLISHER") "Altium Limited"))
      (libsource (lib "Miscellaneous Devices") (part "Res2"))
    )
    (comp (ref "R73")
      (value "20K")
      (footprint "R0603")
      (description "Resistor")
      (fields (field (name "PUBLISHER") "Altium Limited"))
      (libsource (lib "Miscellaneous Devices") (part "Res2"))
    )
    (comp (ref "R74")
      (value "20K")
      (footprint "R0603")
      (description "Resistor")
      (fields (field (name "PUBLISHER") "Altium Limited"))
      (libsource (lib "Miscellaneous Devices") (part "Res2"))
    )
    (comp (ref "R75")
      (value "20K")
      (footprint "R0603")
      (description "Resistor")
      (fields (field (name "PUBLISHER") "Altium Limited"))
      (libsource (lib "Miscellaneous Devices") (part "Res2"))
    )
    (comp (ref "R76")
      (value "20K")
      (footprint "R0603")
      (description "Resistor")
      (fields (field (name "PUBLISHER") "Altium Limited"))
      (libsource (lib "Miscellaneous Devices") (part "Res2"))
    )
    (comp (ref "S0")
      (value "K2-6639SP-C4SC-04")
      (footprint "MY_KEYSOP4")
      (description "Switch")
      (fields (field (name "PUBLISHER") "Altium Limited"))
      (libsource (lib "MYSCH") (part "SW-PB-4pin"))
    )
    (comp (ref "S1")
      (value "K2-6639SP-C4SC-04")
      (footprint "MY_KEYSOP4")
      (description "Switch")
      (fields (field (name "PUBLISHER") "Altium Limited"))
      (libsource (lib "MYSCH") (part "SW-PB-4pin"))
    )
    (comp (ref "S2")
      (value "K2-6639SP-C4SC-04")
      (footprint "MY_KEYSOP4")
      (description "Switch")
      (fields (field (name "PUBLISHER") "Altium Limited"))
      (libsource (lib "MYSCH") (part "SW-PB-4pin"))
    )
    (comp (ref "S_1_C1")
      (value "RS2299")
      (footprint "QFN16")
      (libsource (lib "JTAG批量下载板-V0.5") (part "RS2299"))
    )
    (comp (ref "S_1_C2")
      (value "RS2299")
      (footprint "QFN16")
      (libsource (lib "JTAG批量下载板-V0.5") (part "RS2299"))
    )
    (comp (ref "S_1_C3")
      (value "RS2299")
      (footprint "QFN16")
      (libsource (lib "JTAG批量下载板-V0.5") (part "RS2299"))
    )
    (comp (ref "S_1_C4")
      (value "RS2299")
      (footprint "QFN16")
      (libsource (lib "JTAG批量下载板-V0.5") (part "RS2299"))
    )
    (comp (ref "S_1_C5")
      (value "RS2299")
      (footprint "QFN16")
      (libsource (lib "JTAG批量下载板-V0.5") (part "RS2299"))
    )
    (comp (ref "S_1_C6")
      (value "RS2299")
      (footprint "QFN16")
      (libsource (lib "JTAG批量下载板-V0.5") (part "RS2299"))
    )
    (comp (ref "S_2_C1")
      (value "RS2299")
      (footprint "QFN16")
      (libsource (lib "JTAG批量下载板-V0.5") (part "RS2299"))
    )
    (comp (ref "S_2_C2")
      (value "RS2299")
      (footprint "QFN16")
      (libsource (lib "JTAG批量下载板-V0.5") (part "RS2299"))
    )
    (comp (ref "S_2_C3")
      (value "RS2299")
      (footprint "QFN16")
      (libsource (lib "JTAG批量下载板-V0.5") (part "RS2299"))
    )
    (comp (ref "S_2_C4")
      (value "RS2299")
      (footprint "QFN16")
      (libsource (lib "JTAG批量下载板-V0.5") (part "RS2299"))
    )
    (comp (ref "S_2_C5")
      (value "RS2299")
      (footprint "QFN16")
      (libsource (lib "JTAG批量下载板-V0.5") (part "RS2299"))
    )
    (comp (ref "S_2_C6")
      (value "RS2299")
      (footprint "QFN16")
      (libsource (lib "JTAG批量下载板-V0.5") (part "RS2299"))
    )
    (comp (ref "S_3_C1")
      (value "RS2299")
      (footprint "QFN16")
      (libsource (lib "JTAG批量下载板-V0.5") (part "RS2299"))
    )
    (comp (ref "S_3_C2")
      (value "RS2299")
      (footprint "QFN16")
      (libsource (lib "JTAG批量下载板-V0.5") (part "RS2299"))
    )
    (comp (ref "S_3_C3")
      (value "RS2299")
      (footprint "QFN16")
      (libsource (lib "JTAG批量下载板-V0.5") (part "RS2299"))
    )
    (comp (ref "S_3_C4")
      (value "RS2299")
      (footprint "QFN16")
      (libsource (lib "JTAG批量下载板-V0.5") (part "RS2299"))
    )
    (comp (ref "S_3_C5")
      (value "RS2299")
      (footprint "QFN16")
      (libsource (lib "JTAG批量下载板-V0.5") (part "RS2299"))
    )
    (comp (ref "S_3_C6")
      (value "RS2299")
      (footprint "QFN16")
      (libsource (lib "JTAG批量下载板-V0.5") (part "RS2299"))
    )
    (comp (ref "S_4_C1")
      (value "RS2299")
      (footprint "QFN16")
      (libsource (lib "JTAG批量下载板-V0.5") (part "RS2299"))
    )
    (comp (ref "S_4_C2")
      (value "RS2299")
      (footprint "QFN16")
      (libsource (lib "JTAG批量下载板-V0.5") (part "RS2299"))
    )
    (comp (ref "S_4_C3")
      (value "RS2299")
      (footprint "QFN16")
      (libsource (lib "JTAG批量下载板-V0.5") (part "RS2299"))
    )
    (comp (ref "S_4_C4")
      (value "RS2299")
      (footprint "QFN16")
      (libsource (lib "JTAG批量下载板-V0.5") (part "RS2299"))
    )
    (comp (ref "S_4_C5")
      (value "RS2299")
      (footprint "QFN16")
      (libsource (lib "JTAG批量下载板-V0.5") (part "RS2299"))
    )
    (comp (ref "S_4_C6")
      (value "RS2299")
      (footprint "QFN16")
      (libsource (lib "JTAG批量下载板-V0.5") (part "RS2299"))
    )
    (comp (ref "U2")
      (value "MP2303ADN-LF-Z")
      (footprint "SO-8-EP")
      (libsource (lib "Schlib1") (part "TD1519A"))
    )
    (comp (ref "U3")
      (value "ESDU5V0H4")
      (footprint "SOT-23-6")
      (libsource (lib "Schlib11") (part "CESDLC5V0M5"))
    )
    (comp (ref "U4")
      (value "ME6208A33PG")
      (footprint "SOT89N")
      (libsource (lib "Schlib1") (part "ME6208A50PG"))
    )
    (comp (ref "U5")
      (value "MC74HC595ADR2G")
      (footprint "SOP16_M")
      (libsource (lib "Schlib1") (part "74HC595"))
    )
    (comp (ref "U6")
      (value "STM32F103C8T6")
      (footprint "LQFP-48-1")
      (description "STM32 ARM-based 32-bit MCU with 64 Kbytes Flash, 48-pin LQFP, Industrial Temperature")
      (fields (field (name "PUBLISHER") "Altium Limited"))
      (libsource (lib "ST Microcontroller 32-Bit STM32") (part "STM32F103C8T6"))
    )
    (comp (ref "U14")
      (value "MC74HC595ADR2G")
      (footprint "SOP16_M")
      (libsource (lib "Schlib1") (part "74HC595"))
    )
    (comp (ref "U15")
      (value "MC74HC595ADR2G")
      (footprint "SOP16_M")
      (libsource (lib "Schlib1") (part "74HC595"))
    )
    (comp (ref "U16")
      (value "ME6210A50PG")
      (footprint "SOT89N")
      (libsource (lib "Schlib1") (part "ME6208A50PG"))
    )
    (comp (ref "Y1")
      (value "8M")
      (footprint "CRYSTAL_3.2*2.5")
      (libsource (lib "schlib-yves20140829") (part "CRYSTAL-PASSIVE_3225"))
    )
    (comp (ref "Z1")
      (value "SMBJ12A")
      (footprint "SMB")
      (description "Zener Diode")
      (fields (field (name "PUBLISHER") "Altium Limited"))
      (libsource (lib "Miscellaneous Devices") (part "D Zener"))
    )
  )
  (nets
    (net (code "1") (name "/5V") (class "Default")
      (node (ref "C22") (pin "1") (pinfunction "1_1") (pintype "passive"))
      (node (ref "C23") (pin "2") (pinfunction "2_2") (pintype "passive"))
      (node (ref "P24") (pin "1") (pinfunction "1_1") (pintype "passive"))
      (node (ref "R49") (pin "2") (pinfunction "2_2") (pintype "passive"))
      (node (ref "U16") (pin "3") (pinfunction "VOUT_3") (pintype "passive"))
    )
    (net (code "2") (name "/12V+") (class "Default")
      (node (ref "F1") (pin "2") (pinfunction "2_2") (pintype "passive"))
      (node (ref "L1") (pin "2") (pinfunction "2_2") (pintype "passive"))
      (node (ref "Z1") (pin "K") (pinfunction "K_K") (pintype "passive"))
    )
    (net (code "3") (name "/12V-") (class "Default")
      (node (ref "L2") (pin "2") (pinfunction "2_2") (pintype "passive"))
      (node (ref "P0") (pin "2") (pinfunction "2_2") (pintype "passive"))
      (node (ref "Z1") (pin "A") (pinfunction "A_A") (pintype "passive"))
    )
    (net (code "4") (name "/BEEP_CON") (class "Default")
      (node (ref "R20") (pin "1") (pinfunction "1_1") (pintype "passive"))
      (node (ref "U6") (pin "32") (pinfunction "PA11_32") (pintype "bidirectional"))
    )
    (net (code "5") (name "/BOOT0") (class "Default")
      (node (ref "R14") (pin "2") (pinfunction "2_2") (pintype "passive"))
      (node (ref "U6") (pin "44") (pinfunction "BOOT0_44") (pintype "input"))
    )
    (net (code "6") (name "/BOOT1") (class "Default")
      (node (ref "R17") (pin "2") (pinfunction "2_2") (pintype "passive"))
      (node (ref "U6") (pin "20") (pinfunction "PB2/BOOT1_20") (pintype "bidirectional"))
    )
    (net (code "7") (name "/EN_1_C1") (class "Default")
      (node (ref "P_1_C1") (pin "4") (pinfunction "EN_4") (pintype "passive"))
      (node (ref "S_1_C1") (pin "10") (pinfunction "IN3-4_10") (pintype "passive"))
      (node (ref "S_1_C1") (pin "2") (pinfunction "IN1-2_2") (pintype "passive"))
      (node (ref "U5") (pin "15") (pinfunction "QA_15") (pintype "passive"))
    )
    (net (code "8") (name "/EN_1_C2") (class "Default")
      (node (ref "P_1_C2") (pin "4") (pinfunction "EN_4") (pintype "passive"))
      (node (ref "S_1_C2") (pin "10") (pinfunction "IN3-4_10") (pintype "passive"))
      (node (ref "S_1_C2") (pin "2") (pinfunction "IN1-2_2") (pintype "passive"))
      (node (ref "U5") (pin "4") (pinfunction "QE_4") (pintype "passive"))
    )
    (net (code "9") (name "/EN_1_C3") (class "Default")
      (node (ref "P_1_C3") (pin "4") (pinfunction "EN_4") (pintype "passive"))
      (node (ref "S_1_C3") (pin "10") (pinfunction "IN3-4_10") (pintype "passive"))
      (node (ref "S_1_C3") (pin "2") (pinfunction "IN1-2_2") (pintype "passive"))
      (node (ref "U14") (pin "15") (pinfunction "QA_15") (pintype "passive"))
    )
    (net (code "10") (name "/EN_1_C4") (class "Default")
      (node (ref "P_1_C4") (pin "4") (pinfunction "EN_4") (pintype "passive"))
      (node (ref "S_1_C4") (pin "10") (pinfunction "IN3-4_10") (pintype "passive"))
      (node (ref "S_1_C4") (pin "2") (pinfunction "IN1-2_2") (pintype "passive"))
      (node (ref "U14") (pin "4") (pinfunction "QE_4") (pintype "passive"))
    )
    (net (code "11") (name "/EN_1_C5") (class "Default")
      (node (ref "P_1_C5") (pin "4") (pinfunction "EN_4") (pintype "passive"))
      (node (ref "S_1_C5") (pin "10") (pinfunction "IN3-4_10") (pintype "passive"))
      (node (ref "S_1_C5") (pin "2") (pinfunction "IN1-2_2") (pintype "passive"))
      (node (ref "U15") (pin "15") (pinfunction "QA_15") (pintype "passive"))
    )
    (net (code "12") (name "/EN_1_C6") (class "Default")
      (node (ref "P_1_C6") (pin "4") (pinfunction "EN_4") (pintype "passive"))
      (node (ref "S_1_C6") (pin "10") (pinfunction "IN3-4_10") (pintype "passive"))
      (node (ref "S_1_C6") (pin "2") (pinfunction "IN1-2_2") (pintype "passive"))
      (node (ref "U15") (pin "4") (pinfunction "QE_4") (pintype "passive"))
    )
    (net (code "13") (name "/EN_2_C1") (class "Default")
      (node (ref "P_2_C1") (pin "4") (pinfunction "EN_4") (pintype "passive"))
      (node (ref "S_2_C1") (pin "10") (pinfunction "IN3-4_10") (pintype "passive"))
      (node (ref "S_2_C1") (pin "2") (pinfunction "IN1-2_2") (pintype "passive"))
      (node (ref "U5") (pin "1") (pinfunction "QB_1") (pintype "passive"))
    )
    (net (code "14") (name "/EN_2_C2") (class "Default")
      (node (ref "P_2_C2") (pin "4") (pinfunction "EN_4") (pintype "passive"))
      (node (ref "S_2_C2") (pin "10") (pinfunction "IN3-4_10") (pintype "passive"))
      (node (ref "S_2_C2") (pin "2") (pinfunction "IN1-2_2") (pintype "passive"))
      (node (ref "U5") (pin "5") (pinfunction "QF_5") (pintype "passive"))
    )
    (net (code "15") (name "/EN_2_C3") (class "Default")
      (node (ref "P_2_C3") (pin "4") (pinfunction "EN_4") (pintype "passive"))
      (node (ref "S_2_C3") (pin "10") (pinfunction "IN3-4_10") (pintype "passive"))
      (node (ref "S_2_C3") (pin "2") (pinfunction "IN1-2_2") (pintype "passive"))
      (node (ref "U14") (pin "1") (pinfunction "QB_1") (pintype "passive"))
    )
    (net (code "16") (name "/EN_2_C4") (class "Default")
      (node (ref "P_2_C4") (pin "4") (pinfunction "EN_4") (pintype "passive"))
      (node (ref "S_2_C4") (pin "10") (pinfunction "IN3-4_10") (pintype "passive"))
      (node (ref "S_2_C4") (pin "2") (pinfunction "IN1-2_2") (pintype "passive"))
      (node (ref "U14") (pin "5") (pinfunction "QF_5") (pintype "passive"))
    )
    (net (code "17") (name "/EN_2_C5") (class "Default")
      (node (ref "P_2_C5") (pin "4") (pinfunction "EN_4") (pintype "passive"))
      (node (ref "S_2_C5") (pin "10") (pinfunction "IN3-4_10") (pintype "passive"))
      (node (ref "S_2_C5") (pin "2") (pinfunction "IN1-2_2") (pintype "passive"))
      (node (ref "U15") (pin "1") (pinfunction "QB_1") (pintype "passive"))
    )
    (net (code "18") (name "/EN_2_C6") (class "Default")
      (node (ref "P_2_C6") (pin "4") (pinfunction "EN_4") (pintype "passive"))
      (node (ref "S_2_C6") (pin "10") (pinfunction "IN3-4_10") (pintype "passive"))
      (node (ref "S_2_C6") (pin "2") (pinfunction "IN1-2_2") (pintype "passive"))
      (node (ref "U15") (pin "5") (pinfunction "QF_5") (pintype "passive"))
    )
    (net (code "19") (name "/EN_3_C1") (class "Default")
      (node (ref "P_3_C1") (pin "4") (pinfunction "EN_4") (pintype "passive"))
      (node (ref "S_3_C1") (pin "10") (pinfunction "IN3-4_10") (pintype "passive"))
      (node (ref "S_3_C1") (pin "2") (pinfunction "IN1-2_2") (pintype "passive"))
      (node (ref "U5") (pin "2") (pinfunction "QC_2") (pintype "passive"))
    )
    (net (code "20") (name "/EN_3_C2") (class "Default")
      (node (ref "P_3_C2") (pin "4") (pinfunction "EN_4") (pintype "passive"))
      (node (ref "S_3_C2") (pin "10") (pinfunction "IN3-4_10") (pintype "passive"))
      (node (ref "S_3_C2") (pin "2") (pinfunction "IN1-2_2") (pintype "passive"))
      (node (ref "U5") (pin "6") (pinfunction "QG_6") (pintype "passive"))
    )
    (net (code "21") (name "/EN_3_C3") (class "Default")
      (node (ref "P_3_C3") (pin "4") (pinfunction "EN_4") (pintype "passive"))
      (node (ref "S_3_C3") (pin "10") (pinfunction "IN3-4_10") (pintype "passive"))
      (node (ref "S_3_C3") (pin "2") (pinfunction "IN1-2_2") (pintype "passive"))
      (node (ref "U14") (pin "2") (pinfunction "QC_2") (pintype "passive"))
    )
    (net (code "22") (name "/EN_3_C4") (class "Default")
      (node (ref "P_3_C4") (pin "4") (pinfunction "EN_4") (pintype "passive"))
      (node (ref "S_3_C4") (pin "10") (pinfunction "IN3-4_10") (pintype "passive"))
      (node (ref "S_3_C4") (pin "2") (pinfunction "IN1-2_2") (pintype "passive"))
      (node (ref "U14") (pin "6") (pinfunction "QG_6") (pintype "passive"))
    )
    (net (code "23") (name "/EN_3_C5") (class "Default")
      (node (ref "P_3_C5") (pin "4") (pinfunction "EN_4") (pintype "passive"))
      (node (ref "S_3_C5") (pin "10") (pinfunction "IN3-4_10") (pintype "passive"))
      (node (ref "S_3_C5") (pin "2") (pinfunction "IN1-2_2") (pintype "passive"))
      (node (ref "U15") (pin "2") (pinfunction "QC_2") (pintype "passive"))
    )
    (net (code "24") (name "/EN_3_C6") (class "Default")
      (node (ref "P_3_C6") (pin "4") (pinfunction "EN_4") (pintype "passive"))
      (node (ref "S_3_C6") (pin "10") (pinfunction "IN3-4_10") (pintype "passive"))
      (node (ref "S_3_C6") (pin "2") (pinfunction "IN1-2_2") (pintype "passive"))
      (node (ref "U15") (pin "6") (pinfunction "QG_6") (pintype "passive"))
    )
    (net (code "25") (name "/EN_4_C1") (class "Default")
      (node (ref "P_4_C1") (pin "4") (pinfunction "EN_4") (pintype "passive"))
      (node (ref "S_4_C1") (pin "10") (pinfunction "IN3-4_10") (pintype "passive"))
      (node (ref "S_4_C1") (pin "2") (pinfunction "IN1-2_2") (pintype "passive"))
      (node (ref "U5") (pin "3") (pinfunction "QD_3") (pintype "passive"))
    )
    (net (code "26") (name "/EN_4_C2") (class "Default")
      (node (ref "P_4_C2") (pin "4") (pinfunction "EN_4") (pintype "passive"))
      (node (ref "S_4_C2") (pin "10") (pinfunction "IN3-4_10") (pintype "passive"))
      (node (ref "S_4_C2") (pin "2") (pinfunction "IN1-2_2") (pintype "passive"))
      (node (ref "U5") (pin "7") (pinfunction "QH_7") (pintype "passive"))
    )
    (net (code "27") (name "/EN_4_C3") (class "Default")
      (node (ref "P_4_C3") (pin "4") (pinfunction "EN_4") (pintype "passive"))
      (node (ref "S_4_C3") (pin "10") (pinfunction "IN3-4_10") (pintype "passive"))
      (node (ref "S_4_C3") (pin "2") (pinfunction "IN1-2_2") (pintype "passive"))
      (node (ref "U14") (pin "3") (pinfunction "QD_3") (pintype "passive"))
    )
    (net (code "28") (name "/EN_4_C4") (class "Default")
      (node (ref "P_4_C4") (pin "4") (pinfunction "EN_4") (pintype "passive"))
      (node (ref "S_4_C4") (pin "10") (pinfunction "IN3-4_10") (pintype "passive"))
      (node (ref "S_4_C4") (pin "2") (pinfunction "IN1-2_2") (pintype "passive"))
      (node (ref "U14") (pin "7") (pinfunction "QH_7") (pintype "passive"))
    )
    (net (code "29") (name "/EN_4_C5") (class "Default")
      (node (ref "P_4_C5") (pin "4") (pinfunction "EN_4") (pintype "passive"))
      (node (ref "S_4_C5") (pin "10") (pinfunction "IN3-4_10") (pintype "passive"))
      (node (ref "S_4_C5") (pin "2") (pinfunction "IN1-2_2") (pintype "passive"))
      (node (ref "U15") (pin "3") (pinfunction "QD_3") (pintype "passive"))
    )
    (net (code "30") (name "/EN_4_C6") (class "Default")
      (node (ref "P_4_C6") (pin "4") (pinfunction "EN_4") (pintype "passive"))
      (node (ref "S_4_C6") (pin "10") (pinfunction "IN3-4_10") (pintype "passive"))
      (node (ref "S_4_C6") (pin "2") (pinfunction "IN1-2_2") (pintype "passive"))
      (node (ref "U15") (pin "7") (pinfunction "QH_7") (pintype "passive"))
    )
    (net (code "31") (name "/EN_D1") (class "Default")
      (node (ref "U5") (pin "14") (pinfunction "SER_14") (pintype "passive"))
      (node (ref "U6") (pin "28") (pinfunction "PB15_28") (pintype "bidirectional"))
    )
    (net (code "32") (name "/ISP_RXD") (class "Default")
      (node (ref "P18") (pin "4") (pinfunction "4_4") (pintype "passive"))
      (node (ref "R18") (pin "1") (pinfunction "1_1") (pintype "passive"))
      (node (ref "U3") (pin "6") (pinfunction "6_6") (pintype "passive"))
    )
    (net (code "33") (name "/ISP_TXD") (class "Default")
      (node (ref "P18") (pin "3") (pinfunction "3_3") (pintype "passive"))
      (node (ref "R19") (pin "1") (pinfunction "1_1") (pintype "passive"))
      (node (ref "U3") (pin "4") (pinfunction "4_4") (pintype "passive"))
    )
    (net (code "34") (name "/JTAG_3.3V") (class "Default")
      (node (ref "J1") (pin "1") (pinfunction "1_1") (pintype "passive"))
    )
    (net (code "35") (name "/JTAG_BUSY") (class "Default")
      (node (ref "R5") (pin "2") (pinfunction "2_2") (pintype "passive"))
      (node (ref "U6") (pin "45") (pinfunction "PB8_45") (pintype "bidirectional"))
    )
    (net (code "36") (name "/JTAG_FAIL") (class "Default")
      (node (ref "R9") (pin "2") (pinfunction "2_2") (pintype "passive"))
      (node (ref "U6") (pin "46") (pinfunction "PB9_46") (pintype "bidirectional"))
    )
    (net (code "37") (name "/JTAG_OK") (class "Default")
      (node (ref "R2") (pin "2") (pinfunction "2_2") (pintype "passive"))
      (node (ref "U6") (pin "43") (pinfunction "PB7_43") (pintype "bidirectional"))
    )
    (net (code "38") (name "/JTAG_START") (class "Default")
      (node (ref "R1") (pin "2") (pinfunction "2_2") (pintype "passive"))
      (node (ref "U6") (pin "42") (pinfunction "PB6_42") (pintype "bidirectional"))
    )
    (net (code "39") (name "/JTAG_TCK") (class "Default")
      (node (ref "JTAG") (pin "4") (pinfunction "JTAG_TCK_4") (pintype "passive"))
      (node (ref "S_1_C1") (pin "8") (pinfunction "COM3_8") (pintype "passive"))
      (node (ref "S_1_C2") (pin "8") (pinfunction "COM3_8") (pintype "passive"))
      (node (ref "S_1_C3") (pin "8") (pinfunction "COM3_8") (pintype "passive"))
      (node (ref "S_1_C4") (pin "8") (pinfunction "COM3_8") (pintype "passive"))
      (node (ref "S_1_C5") (pin "8") (pinfunction "COM3_8") (pintype "passive"))
      (node (ref "S_1_C6") (pin "8") (pinfunction "COM3_8") (pintype "passive"))
      (node (ref "S_2_C1") (pin "8") (pinfunction "COM3_8") (pintype "passive"))
      (node (ref "S_2_C2") (pin "8") (pinfunction "COM3_8") (pintype "passive"))
      (node (ref "S_2_C3") (pin "8") (pinfunction "COM3_8") (pintype "passive"))
      (node (ref "S_2_C4") (pin "8") (pinfunction "COM3_8") (pintype "passive"))
      (node (ref "S_2_C5") (pin "8") (pinfunction "COM3_8") (pintype "passive"))
      (node (ref "S_2_C6") (pin "8") (pinfunction "COM3_8") (pintype "passive"))
      (node (ref "S_3_C1") (pin "8") (pinfunction "COM3_8") (pintype "passive"))
      (node (ref "S_3_C2") (pin "8") (pinfunction "COM3_8") (pintype "passive"))
      (node (ref "S_3_C3") (pin "8") (pinfunction "COM3_8") (pintype "passive"))
      (node (ref "S_3_C4") (pin "8") (pinfunction "COM3_8") (pintype "passive"))
      (node (ref "S_3_C5") (pin "8") (pinfunction "COM3_8") (pintype "passive"))
      (node (ref "S_3_C6") (pin "8") (pinfunction "COM3_8") (pintype "passive"))
      (node (ref "S_4_C1") (pin "8") (pinfunction "COM3_8") (pintype "passive"))
      (node (ref "S_4_C2") (pin "8") (pinfunction "COM3_8") (pintype "passive"))
      (node (ref "S_4_C3") (pin "8") (pinfunction "COM3_8") (pintype "passive"))
      (node (ref "S_4_C4") (pin "8") (pinfunction "COM3_8") (pintype "passive"))
      (node (ref "S_4_C5") (pin "8") (pinfunction "COM3_8") (pintype "passive"))
      (node (ref "S_4_C6") (pin "8") (pinfunction "COM3_8") (pintype "passive"))
    )
    (net (code "40") (name "/JTAG_TDI") (class "Default")
      (node (ref "JTAG") (pin "3") (pinfunction "JTAG_TDI_3") (pintype "passive"))
      (node (ref "S_1_C1") (pin "4") (pinfunction "COM2_4") (pintype "passive"))
      (node (ref "S_1_C2") (pin "4") (pinfunction "COM2_4") (pintype "passive"))
      (node (ref "S_1_C3") (pin "4") (pinfunction "COM2_4") (pintype "passive"))
      (node (ref "S_1_C4") (pin "4") (pinfunction "COM2_4") (pintype "passive"))
      (node (ref "S_1_C5") (pin "4") (pinfunction "COM2_4") (pintype "passive"))
      (node (ref "S_1_C6") (pin "4") (pinfunction "COM2_4") (pintype "passive"))
      (node (ref "S_2_C1") (pin "4") (pinfunction "COM2_4") (pintype "passive"))
      (node (ref "S_2_C2") (pin "4") (pinfunction "COM2_4") (pintype "passive"))
      (node (ref "S_2_C3") (pin "4") (pinfunction "COM2_4") (pintype "passive"))
      (node (ref "S_2_C4") (pin "4") (pinfunction "COM2_4") (pintype "passive"))
      (node (ref "S_2_C5") (pin "4") (pinfunction "COM2_4") (pintype "passive"))
      (node (ref "S_2_C6") (pin "4") (pinfunction "COM2_4") (pintype "passive"))
      (node (ref "S_3_C1") (pin "4") (pinfunction "COM2_4") (pintype "passive"))
      (node (ref "S_3_C2") (pin "4") (pinfunction "COM2_4") (pintype "passive"))
      (node (ref "S_3_C3") (pin "4") (pinfunction "COM2_4") (pintype "passive"))
      (node (ref "S_3_C4") (pin "4") (pinfunction "COM2_4") (pintype "passive"))
      (node (ref "S_3_C5") (pin "4") (pinfunction "COM2_4") (pintype "passive"))
      (node (ref "S_3_C6") (pin "4") (pinfunction "COM2_4") (pintype "passive"))
      (node (ref "S_4_C1") (pin "4") (pinfunction "COM2_4") (pintype "passive"))
      (node (ref "S_4_C2") (pin "4") (pinfunction "COM2_4") (pintype "passive"))
      (node (ref "S_4_C3") (pin "4") (pinfunction "COM2_4") (pintype "passive"))
      (node (ref "S_4_C4") (pin "4") (pinfunction "COM2_4") (pintype "passive"))
      (node (ref "S_4_C5") (pin "4") (pinfunction "COM2_4") (pintype "passive"))
      (node (ref "S_4_C6") (pin "4") (pinfunction "COM2_4") (pintype "passive"))
    )
    (net (code "41") (name "/JTAG_TDO") (class "Default")
      (node (ref "JTAG") (pin "2") (pinfunction "JTAG_TDO_2") (pintype "passive"))
      (node (ref "S_1_C1") (pin "16") (pinfunction "COM1_16") (pintype "passive"))
      (node (ref "S_1_C2") (pin "16") (pinfunction "COM1_16") (pintype "passive"))
      (node (ref "S_1_C3") (pin "16") (pinfunction "COM1_16") (pintype "passive"))
      (node (ref "S_1_C4") (pin "16") (pinfunction "COM1_16") (pintype "passive"))
      (node (ref "S_1_C5") (pin "16") (pinfunction "COM1_16") (pintype "passive"))
      (node (ref "S_1_C6") (pin "16") (pinfunction "COM1_16") (pintype "passive"))
      (node (ref "S_2_C1") (pin "16") (pinfunction "COM1_16") (pintype "passive"))
      (node (ref "S_2_C2") (pin "16") (pinfunction "COM1_16") (pintype "passive"))
      (node (ref "S_2_C3") (pin "16") (pinfunction "COM1_16") (pintype "passive"))
      (node (ref "S_2_C4") (pin "16") (pinfunction "COM1_16") (pintype "passive"))
      (node (ref "S_2_C5") (pin "16") (pinfunction "COM1_16") (pintype "passive"))
      (node (ref "S_2_C6") (pin "16") (pinfunction "COM1_16") (pintype "passive"))
      (node (ref "S_3_C1") (pin "16") (pinfunction "COM1_16") (pintype "passive"))
      (node (ref "S_3_C2") (pin "16") (pinfunction "COM1_16") (pintype "passive"))
      (node (ref "S_3_C3") (pin "16") (pinfunction "COM1_16") (pintype "passive"))
      (node (ref "S_3_C4") (pin "16") (pinfunction "COM1_16") (pintype "passive"))
      (node (ref "S_3_C5") (pin "16") (pinfunction "COM1_16") (pintype "passive"))
      (node (ref "S_3_C6") (pin "16") (pinfunction "COM1_16") (pintype "passive"))
      (node (ref "S_4_C1") (pin "16") (pinfunction "COM1_16") (pintype "passive"))
      (node (ref "S_4_C2") (pin "16") (pinfunction "COM1_16") (pintype "passive"))
      (node (ref "S_4_C3") (pin "16") (pinfunction "COM1_16") (pintype "passive"))
      (node (ref "S_4_C4") (pin "16") (pinfunction "COM1_16") (pintype "passive"))
      (node (ref "S_4_C5") (pin "16") (pinfunction "COM1_16") (pintype "passive"))
      (node (ref "S_4_C6") (pin "16") (pinfunction "COM1_16") (pintype "passive"))
    )
    (net (code "42") (name "/JTAG_TMS") (class "Default")
      (node (ref "JTAG") (pin "5") (pinfunction "JTAG_TMS_5") (pintype "passive"))
      (node (ref "S_1_C1") (pin "12") (pinfunction "COM4_12") (pintype "passive"))
      (node (ref "S_1_C2") (pin "12") (pinfunction "COM4_12") (pintype "passive"))
      (node (ref "S_1_C3") (pin "12") (pinfunction "COM4_12") (pintype "passive"))
      (node (ref "S_1_C4") (pin "12") (pinfunction "COM4_12") (pintype "passive"))
      (node (ref "S_1_C5") (pin "12") (pinfunction "COM4_12") (pintype "passive"))
      (node (ref "S_1_C6") (pin "12") (pinfunction "COM4_12") (pintype "passive"))
      (node (ref "S_2_C1") (pin "12") (pinfunction "COM4_12") (pintype "passive"))
      (node (ref "S_2_C2") (pin "12") (pinfunction "COM4_12") (pintype "passive"))
      (node (ref "S_2_C3") (pin "12") (pinfunction "COM4_12") (pintype "passive"))
      (node (ref "S_2_C4") (pin "12") (pinfunction "COM4_12") (pintype "passive"))
      (node (ref "S_2_C5") (pin "12") (pinfunction "COM4_12") (pintype "passive"))
      (node (ref "S_2_C6") (pin "12") (pinfunction "COM4_12") (pintype "passive"))
      (node (ref "S_3_C1") (pin "12") (pinfunction "COM4_12") (pintype "passive"))
      (node (ref "S_3_C2") (pin "12") (pinfunction "COM4_12") (pintype "passive"))
      (node (ref "S_3_C3") (pin "12") (pinfunction "COM4_12") (pintype "passive"))
      (node (ref "S_3_C4") (pin "12") (pinfunction "COM4_12") (pintype "passive"))
      (node (ref "S_3_C5") (pin "12") (pinfunction "COM4_12") (pintype "passive"))
      (node (ref "S_3_C6") (pin "12") (pinfunction "COM4_12") (pintype "passive"))
      (node (ref "S_4_C1") (pin "12") (pinfunction "COM4_12") (pintype "passive"))
      (node (ref "S_4_C2") (pin "12") (pinfunction "COM4_12") (pintype "passive"))
      (node (ref "S_4_C3") (pin "12") (pinfunction "COM4_12") (pintype "passive"))
      (node (ref "S_4_C4") (pin "12") (pinfunction "COM4_12") (pintype "passive"))
      (node (ref "S_4_C5") (pin "12") (pinfunction "COM4_12") (pintype "passive"))
      (node (ref "S_4_C6") (pin "12") (pinfunction "COM4_12") (pintype "passive"))
    )
    (net (code "43") (name "/KEY_1") (class "Default")
      (node (ref "C38") (pin "2") (pinfunction "2_2") (pintype "passive"))
      (node (ref "R36") (pin "1") (pinfunction "1_1") (pintype "passive"))
      (node (ref "R40") (pin "1") (pinfunction "1_1") (pintype "passive"))
      (node (ref "U6") (pin "4") (pinfunction "PC15-OSC32_OUT_4") (pintype "bidirectional"))
    )
    (net (code "44") (name "/KEY_2") (class "Default")
      (node (ref "C39") (pin "2") (pinfunction "2_2") (pintype "passive"))
      (node (ref "R37") (pin "1") (pinfunction "1_1") (pintype "passive"))
      (node (ref "R41") (pin "1") (pinfunction "1_1") (pintype "passive"))
      (node (ref "U6") (pin "3") (pinfunction "PC14-OSC32_IN_3") (pintype "bidirectional"))
    )
    (net (code "45") (name "/LCD_RXD") (class "Default")
      (node (ref "P24") (pin "2") (pinfunction "2_2") (pintype "passive"))
      (node (ref "R49") (pin "1") (pinfunction "1_1") (pintype "passive"))
      (node (ref "R50") (pin "1") (pinfunction "1_1") (pintype "passive"))
    )
    (net (code "46") (name "/LCD_TXD") (class "Default")
      (node (ref "P24") (pin "3") (pinfunction "3_3") (pintype "passive"))
      (node (ref "R47") (pin "1") (pinfunction "1_1") (pintype "passive"))
    )
    (net (code "47") (name "/MCU_RX1") (class "Default")
      (node (ref "R19") (pin "2") (pinfunction "2_2") (pintype "passive"))
      (node (ref "U6") (pin "31") (pinfunction "PA10_31") (pintype "bidirectional"))
    )
    (net (code "48") (name "/MCU_RX2") (class "Default")
      (node (ref "R47") (pin "2") (pinfunction "2_2") (pintype "passive"))
      (node (ref "R48") (pin "2") (pinfunction "2_2") (pintype "passive"))
      (node (ref "U6") (pin "13") (pinfunction "PA3_13") (pintype "bidirectional"))
    )
    (net (code "49") (name "/MCU_RX3") (class "Default")
      (node (ref "R44") (pin "2") (pinfunction "2_2") (pintype "passive"))
      (node (ref "R45") (pin "2") (pinfunction "2_2") (pintype "passive"))
      (node (ref "U6") (pin "22") (pinfunction "PB11_22") (pintype "bidirectional"))
    )
    (net (code "50") (name "/MCU_TX1") (class "Default")
      (node (ref "R18") (pin "2") (pinfunction "2_2") (pintype "passive"))
      (node (ref "U6") (pin "30") (pinfunction "PA9_30") (pintype "bidirectional"))
    )
    (net (code "51") (name "/MCU_TX2") (class "Default")
      (node (ref "R50") (pin "2") (pinfunction "2_2") (pintype "passive"))
      (node (ref "U6") (pin "12") (pinfunction "PA2_12") (pintype "bidirectional"))
    )
    (net (code "52") (name "/MCU_TX3") (class "Default")
      (node (ref "R51") (pin "2") (pinfunction "2_2") (pintype "passive"))
      (node (ref "U6") (pin "21") (pinfunction "PB10_21") (pintype "bidirectional"))
    )
    (net (code "53") (name "/NRST") (class "Default")
      (node (ref "C26") (pin "1") (pinfunction "1_1") (pintype "passive"))
      (node (ref "R12") (pin "1") (pinfunction "1_1") (pintype "passive"))
      (node (ref "S0") (pin "1") (pinfunction "1_1") (pintype "passive"))
      (node (ref "S0") (pin "2") (pinfunction "2_2") (pintype "passive"))
      (node (ref "U6") (pin "7") (pinfunction "NRST_7") (pintype "bidirectional"))
    )
    (net (code "54") (name "/OSC_IN") (class "Default")
      (node (ref "C24") (pin "1") (pinfunction "1_1") (pintype "passive"))
      (node (ref "R11") (pin "1") (pinfunction "1_1") (pintype "passive"))
      (node (ref "U6") (pin "5") (pinfunction "OSC_IN/PD0_5") (pintype "input"))
      (node (ref "Y1") (pin "3") (pinfunction "OUTPUT_3") (pintype "passive"))
    )
    (net (code "55") (name "/OSC_OUT") (class "Default")
      (node (ref "C25") (pin "1") (pinfunction "1_1") (pintype "passive"))
      (node (ref "R11") (pin "2") (pinfunction "2_2") (pintype "passive"))
      (node (ref "U6") (pin "6") (pinfunction "OSC_OUT/PD1_6") (pintype "output"))
      (node (ref "Y1") (pin "1") (pinfunction "INPUT_1") (pintype "passive"))
    )
    (net (code "56") (name "/PRT_DTR") (class "Default")
      (node (ref "R43") (pin "2") (pinfunction "2_2") (pintype "passive"))
      (node (ref "U6") (pin "17") (pinfunction "PA7_17") (pintype "bidirectional"))
    )
    (net (code "57") (name "/PRT_RXD") (class "Default")
      (node (ref "P23") (pin "4") (pinfunction "4_4") (pintype "passive"))
      (node (ref "R51") (pin "1") (pinfunction "1_1") (pintype "passive"))
    )
    (net (code "58") (name "/PRT_TXD") (class "Default")
      (node (ref "P23") (pin "3") (pinfunction "3_3") (pintype "passive"))
      (node (ref "R44") (pin "1") (pinfunction "1_1") (pintype "passive"))
    )
    (net (code "59") (name "/PW_1_C1") (class "Default")
      (node (ref "P1_C1") (pin "1") (pinfunction "1_1") (pintype "passive"))
      (node (ref "P_1_C1") (pin "1") (pinfunction "VOUT_1") (pintype "passive"))
    )
    (net (code "60") (name "/PW_1_C2") (class "Default")
      (node (ref "P1_C2") (pin "1") (pinfunction "1_1") (pintype "passive"))
      (node (ref "P_1_C2") (pin "1") (pinfunction "VOUT_1") (pintype "passive"))
    )
    (net (code "61") (name "/PW_1_C3") (class "Default")
      (node (ref "P1_C3") (pin "1") (pinfunction "1_1") (pintype "passive"))
      (node (ref "P_1_C3") (pin "1") (pinfunction "VOUT_1") (pintype "passive"))
    )
    (net (code "62") (name "/PW_1_C4") (class "Default")
      (node (ref "P1_C4") (pin "1") (pinfunction "1_1") (pintype "passive"))
      (node (ref "P_1_C4") (pin "1") (pinfunction "VOUT_1") (pintype "passive"))
    )
    (net (code "63") (name "/PW_1_C5") (class "Default")
      (node (ref "P1_C5") (pin "1") (pinfunction "1_1") (pintype "passive"))
      (node (ref "P_1_C5") (pin "1") (pinfunction "VOUT_1") (pintype "passive"))
    )
    (net (code "64") (name "/PW_1_C6") (class "Default")
      (node (ref "P1_C6") (pin "1") (pinfunction "1_1") (pintype "passive"))
      (node (ref "P_1_C6") (pin "1") (pinfunction "VOUT_1") (pintype "passive"))
    )
    (net (code "65") (name "/PW_2_C1") (class "Default")
      (node (ref "P2_C1") (pin "1") (pinfunction "1_1") (pintype "passive"))
      (node (ref "P_2_C1") (pin "1") (pinfunction "VOUT_1") (pintype "passive"))
    )
    (net (code "66") (name "/PW_2_C2") (class "Default")
      (node (ref "P2_C2") (pin "1") (pinfunction "1_1") (pintype "passive"))
      (node (ref "P_2_C2") (pin "1") (pinfunction "VOUT_1") (pintype "passive"))
    )
    (net (code "67") (name "/PW_2_C3") (class "Default")
      (node (ref "P2_C3") (pin "1") (pinfunction "1_1") (pintype "passive"))
      (node (ref "P_2_C3") (pin "1") (pinfunction "VOUT_1") (pintype "passive"))
    )
    (net (code "68") (name "/PW_2_C4") (class "Default")
      (node (ref "P2_C4") (pin "1") (pinfunction "1_1") (pintype "passive"))
      (node (ref "P_2_C4") (pin "1") (pinfunction "VOUT_1") (pintype "passive"))
    )
    (net (code "69") (name "/PW_2_C5") (class "Default")
      (node (ref "P2_C5") (pin "1") (pinfunction "1_1") (pintype "passive"))
      (node (ref "P_2_C5") (pin "1") (pinfunction "VOUT_1") (pintype "passive"))
    )
    (net (code "70") (name "/PW_2_C6") (class "Default")
      (node (ref "P2_C6") (pin "1") (pinfunction "1_1") (pintype "passive"))
      (node (ref "P_2_C6") (pin "1") (pinfunction "VOUT_1") (pintype "passive"))
    )
    (net (code "71") (name "/PW_3_C1") (class "Default")
      (node (ref "P3_C1") (pin "1") (pinfunction "1_1") (pintype "passive"))
      (node (ref "P_3_C1") (pin "1") (pinfunction "VOUT_1") (pintype "passive"))
    )
    (net (code "72") (name "/PW_3_C2") (class "Default")
      (node (ref "P3_C2") (pin "1") (pinfunction "1_1") (pintype "passive"))
      (node (ref "P_3_C2") (pin "1") (pinfunction "VOUT_1") (pintype "passive"))
    )
    (net (code "73") (name "/PW_3_C3") (class "Default")
      (node (ref "P3_C3") (pin "1") (pinfunction "1_1") (pintype "passive"))
      (node (ref "P_3_C3") (pin "1") (pinfunction "VOUT_1") (pintype "passive"))
    )
    (net (code "74") (name "/PW_3_C4") (class "Default")
      (node (ref "P3_C4") (pin "1") (pinfunction "1_1") (pintype "passive"))
      (node (ref "P_3_C4") (pin "1") (pinfunction "VOUT_1") (pintype "passive"))
    )
    (net (code "75") (name "/PW_3_C5") (class "Default")
      (node (ref "P3_C5") (pin "1") (pinfunction "1_1") (pintype "passive"))
      (node (ref "P_3_C5") (pin "1") (pinfunction "VOUT_1") (pintype "passive"))
    )
    (net (code "76") (name "/PW_3_C6") (class "Default")
      (node (ref "P3_C6") (pin "1") (pinfunction "1_1") (pintype "passive"))
      (node (ref "P_3_C6") (pin "1") (pinfunction "VOUT_1") (pintype "passive"))
    )
    (net (code "77") (name "/PW_4_C1") (class "Default")
      (node (ref "P4_C1") (pin "1") (pinfunction "1_1") (pintype "passive"))
      (node (ref "P_4_C1") (pin "1") (pinfunction "VOUT_1") (pintype "passive"))
    )
    (net (code "78") (name "/PW_4_C2") (class "Default")
      (node (ref "P4_C2") (pin "1") (pinfunction "1_1") (pintype "passive"))
      (node (ref "P_4_C2") (pin "1") (pinfunction "VOUT_1") (pintype "passive"))
    )
    (net (code "79") (name "/PW_4_C3") (class "Default")
      (node (ref "P4_C3") (pin "1") (pinfunction "1_1") (pintype "passive"))
      (node (ref "P_4_C3") (pin "1") (pinfunction "VOUT_1") (pintype "passive"))
    )
    (net (code "80") (name "/PW_4_C4") (class "Default")
      (node (ref "P4_C4") (pin "1") (pinfunction "1_1") (pintype "passive"))
      (node (ref "P_4_C4") (pin "1") (pinfunction "VOUT_1") (pintype "passive"))
    )
    (net (code "81") (name "/PW_4_C5") (class "Default")
      (node (ref "P4_C5") (pin "1") (pinfunction "1_1") (pintype "passive"))
      (node (ref "P_4_C5") (pin "1") (pinfunction "VOUT_1") (pintype "passive"))
    )
    (net (code "82") (name "/PW_4_C6") (class "Default")
      (node (ref "P4_C6") (pin "1") (pinfunction "1_1") (pintype "passive"))
      (node (ref "P_4_C6") (pin "1") (pinfunction "VOUT_1") (pintype "passive"))
    )
    (net (code "83") (name "/QH1'") (class "Default")
      (node (ref "U14") (pin "14") (pinfunction "SER_14") (pintype "passive"))
      (node (ref "U5") (pin "9") (pinfunction "QH'_9") (pintype "passive"))
    )
    (net (code "84") (name "/QH2'") (class "Default")
      (node (ref "U14") (pin "9") (pinfunction "QH'_9") (pintype "passive"))
      (node (ref "U15") (pin "14") (pinfunction "SER_14") (pintype "passive"))
    )
    (net (code "85") (name "/RCLK_1") (class "Default")
      (node (ref "U14") (pin "12") (pinfunction "RCLK_12") (pintype "passive"))
      (node (ref "U15") (pin "12") (pinfunction "RCLK_12") (pintype "passive"))
      (node (ref "U5") (pin "12") (pinfunction "RCLK_12") (pintype "passive"))
      (node (ref "U6") (pin "29") (pinfunction "PA8_29") (pintype "bidirectional"))
    )
    (net (code "86") (name "/SRCLK_1") (class "Default")
      (node (ref "U14") (pin "11") (pinfunction "SRCLK_11") (pintype "passive"))
      (node (ref "U15") (pin "11") (pinfunction "SRCLK_11") (pintype "passive"))
      (node (ref "U5") (pin "11") (pinfunction "SRCLK_11") (pintype "passive"))
      (node (ref "U6") (pin "27") (pinfunction "PB14_27") (pintype "bidirectional"))
    )
    (net (code "87") (name "/SWCLK") (class "Default")
      (node (ref "P17") (pin "4") (pinfunction "4_4") (pintype "passive"))
      (node (ref "U3") (pin "1") (pinfunction "1_1") (pintype "passive"))
      (node (ref "U6") (pin "37") (pinfunction "PA14/JTCK/SWCLK_37") (pintype "bidirectional"))
    )
    (net (code "88") (name "/SWDIO") (class "Default")
      (node (ref "P17") (pin "3") (pinfunction "3_3") (pintype "passive"))
      (node (ref "U3") (pin "3") (pinfunction "3_3") (pintype "passive"))
      (node (ref "U6") (pin "34") (pinfunction "PA13/JTMS/SWDIO_34") (pintype "bidirectional"))
    )
    (net (code "89") (name "/TCK_1_C1") (class "Default")
      (node (ref "P1_C1") (pin "4") (pinfunction "4_4") (pintype "passive"))
      (node (ref "S_1_C1") (pin "7") (pinfunction "NO3_7") (pintype "passive"))
    )
    (net (code "90") (name "/TCK_1_C2") (class "Default")
      (node (ref "P1_C2") (pin "4") (pinfunction "4_4") (pintype "passive"))
      (node (ref "S_1_C2") (pin "7") (pinfunction "NO3_7") (pintype "passive"))
    )
    (net (code "91") (name "/TCK_1_C3") (class "Default")
      (node (ref "P1_C3") (pin "4") (pinfunction "4_4") (pintype "passive"))
      (node (ref "S_1_C3") (pin "7") (pinfunction "NO3_7") (pintype "passive"))
    )
    (net (code "92") (name "/TCK_1_C4") (class "Default")
      (node (ref "P1_C4") (pin "4") (pinfunction "4_4") (pintype "passive"))
      (node (ref "S_1_C4") (pin "7") (pinfunction "NO3_7") (pintype "passive"))
    )
    (net (code "93") (name "/TCK_1_C5") (class "Default")
      (node (ref "P1_C5") (pin "4") (pinfunction "4_4") (pintype "passive"))
      (node (ref "S_1_C5") (pin "7") (pinfunction "NO3_7") (pintype "passive"))
    )
    (net (code "94") (name "/TCK_1_C6") (class "Default")
      (node (ref "P1_C6") (pin "4") (pinfunction "4_4") (pintype "passive"))
      (node (ref "S_1_C6") (pin "7") (pinfunction "NO3_7") (pintype "passive"))
    )
    (net (code "95") (name "/TCK_2_C1") (class "Default")
      (node (ref "P2_C1") (pin "4") (pinfunction "4_4") (pintype "passive"))
      (node (ref "S_2_C1") (pin "7") (pinfunction "NO3_7") (pintype "passive"))
    )
    (net (code "96") (name "/TCK_2_C2") (class "Default")
      (node (ref "P2_C2") (pin "4") (pinfunction "4_4") (pintype "passive"))
      (node (ref "S_2_C2") (pin "7") (pinfunction "NO3_7") (pintype "passive"))
    )
    (net (code "97") (name "/TCK_2_C3") (class "Default")
      (node (ref "P2_C3") (pin "4") (pinfunction "4_4") (pintype "passive"))
      (node (ref "S_2_C3") (pin "7") (pinfunction "NO3_7") (pintype "passive"))
    )
    (net (code "98") (name "/TCK_2_C4") (class "Default")
      (node (ref "P2_C4") (pin "4") (pinfunction "4_4") (pintype "passive"))
      (node (ref "S_2_C4") (pin "7") (pinfunction "NO3_7") (pintype "passive"))
    )
    (net (code "99") (name "/TCK_2_C5") (class "Default")
      (node (ref "P2_C5") (pin "4") (pinfunction "4_4") (pintype "passive"))
      (node (ref "S_2_C5") (pin "7") (pinfunction "NO3_7") (pintype "passive"))
    )
    (net (code "100") (name "/TCK_2_C6") (class "Default")
      (node (ref "P2_C6") (pin "4") (pinfunction "4_4") (pintype "passive"))
      (node (ref "S_2_C6") (pin "7") (pinfunction "NO3_7") (pintype "passive"))
    )
    (net (code "101") (name "/TCK_3_C1") (class "Default")
      (node (ref "P3_C1") (pin "4") (pinfunction "4_4") (pintype "passive"))
      (node (ref "S_3_C1") (pin "7") (pinfunction "NO3_7") (pintype "passive"))
    )
    (net (code "102") (name "/TCK_3_C2") (class "Default")
      (node (ref "P3_C2") (pin "4") (pinfunction "4_4") (pintype "passive"))
      (node (ref "S_3_C2") (pin "7") (pinfunction "NO3_7") (pintype "passive"))
    )
    (net (code "103") (name "/TCK_3_C3") (class "Default")
      (node (ref "P3_C3") (pin "4") (pinfunction "4_4") (pintype "passive"))
      (node (ref "S_3_C3") (pin "7") (pinfunction "NO3_7") (pintype "passive"))
    )
    (net (code "104") (name "/TCK_3_C4") (class "Default")
      (node (ref "P3_C4") (pin "4") (pinfunction "4_4") (pintype "passive"))
      (node (ref "S_3_C4") (pin "7") (pinfunction "NO3_7") (pintype "passive"))
    )
    (net (code "105") (name "/TCK_3_C5") (class "Default")
      (node (ref "P3_C5") (pin "4") (pinfunction "4_4") (pintype "passive"))
      (node (ref "S_3_C5") (pin "7") (pinfunction "NO3_7") (pintype "passive"))
    )
    (net (code "106") (name "/TCK_3_C6") (class "Default")
      (node (ref "P3_C6") (pin "4") (pinfunction "4_4") (pintype "passive"))
      (node (ref "S_3_C6") (pin "7") (pinfunction "NO3_7") (pintype "passive"))
    )
    (net (code "107") (name "/TCK_4_C1") (class "Default")
      (node (ref "P4_C1") (pin "4") (pinfunction "4_4") (pintype "passive"))
      (node (ref "S_4_C1") (pin "7") (pinfunction "NO3_7") (pintype "passive"))
    )
    (net (code "108") (name "/TCK_4_C2") (class "Default")
      (node (ref "P4_C2") (pin "4") (pinfunction "4_4") (pintype "passive"))
      (node (ref "S_4_C2") (pin "7") (pinfunction "NO3_7") (pintype "passive"))
    )
    (net (code "109") (name "/TCK_4_C3") (class "Default")
      (node (ref "P4_C3") (pin "4") (pinfunction "4_4") (pintype "passive"))
      (node (ref "S_4_C3") (pin "7") (pinfunction "NO3_7") (pintype "passive"))
    )
    (net (code "110") (name "/TCK_4_C4") (class "Default")
      (node (ref "P4_C4") (pin "4") (pinfunction "4_4") (pintype "passive"))
      (node (ref "S_4_C4") (pin "7") (pinfunction "NO3_7") (pintype "passive"))
    )
    (net (code "111") (name "/TCK_4_C5") (class "Default")
      (node (ref "P4_C5") (pin "4") (pinfunction "4_4") (pintype "passive"))
      (node (ref "S_4_C5") (pin "7") (pinfunction "NO3_7") (pintype "passive"))
    )
    (net (code "112") (name "/TCK_4_C6") (class "Default")
      (node (ref "P4_C6") (pin "4") (pinfunction "4_4") (pintype "passive"))
      (node (ref "S_4_C6") (pin "7") (pinfunction "NO3_7") (pintype "passive"))
    )
    (net (code "113") (name "/TDI_1_C1") (class "Default")
      (node (ref "P1_C1") (pin "3") (pinfunction "3_3") (pintype "passive"))
      (node (ref "S_1_C1") (pin "3") (pinfunction "NO2_3") (pintype "passive"))
    )
    (net (code "114") (name "/TDI_1_C2") (class "Default")
      (node (ref "P1_C2") (pin "3") (pinfunction "3_3") (pintype "passive"))
      (node (ref "S_1_C2") (pin "3") (pinfunction "NO2_3") (pintype "passive"))
    )
    (net (code "115") (name "/TDI_1_C3") (class "Default")
      (node (ref "P1_C3") (pin "3") (pinfunction "3_3") (pintype "passive"))
      (node (ref "S_1_C3") (pin "3") (pinfunction "NO2_3") (pintype "passive"))
    )
    (net (code "116") (name "/TDI_1_C4") (class "Default")
      (node (ref "P1_C4") (pin "3") (pinfunction "3_3") (pintype "passive"))
      (node (ref "S_1_C4") (pin "3") (pinfunction "NO2_3") (pintype "passive"))
    )
    (net (code "117") (name "/TDI_1_C5") (class "Default")
      (node (ref "P1_C5") (pin "3") (pinfunction "3_3") (pintype "passive"))
      (node (ref "S_1_C5") (pin "3") (pinfunction "NO2_3") (pintype "passive"))
    )
    (net (code "118") (name "/TDI_1_C6") (class "Default")
      (node (ref "P1_C6") (pin "3") (pinfunction "3_3") (pintype "passive"))
      (node (ref "S_1_C6") (pin "3") (pinfunction "NO2_3") (pintype "passive"))
    )
    (net (code "119") (name "/TDI_2_C1") (class "Default")
      (node (ref "P2_C1") (pin "3") (pinfunction "3_3") (pintype "passive"))
      (node (ref "S_2_C1") (pin "3") (pinfunction "NO2_3") (pintype "passive"))
    )
    (net (code "120") (name "/TDI_2_C2") (class "Default")
      (node (ref "P2_C2") (pin "3") (pinfunction "3_3") (pintype "passive"))
      (node (ref "S_2_C2") (pin "3") (pinfunction "NO2_3") (pintype "passive"))
    )
    (net (code "121") (name "/TDI_2_C3") (class "Default")
      (node (ref "P2_C3") (pin "3") (pinfunction "3_3") (pintype "passive"))
      (node (ref "S_2_C3") (pin "3") (pinfunction "NO2_3") (pintype "passive"))
    )
    (net (code "122") (name "/TDI_2_C4") (class "Default")
      (node (ref "P2_C4") (pin "3") (pinfunction "3_3") (pintype "passive"))
      (node (ref "S_2_C4") (pin "3") (pinfunction "NO2_3") (pintype "passive"))
    )
    (net (code "123") (name "/TDI_2_C5") (class "Default")
      (node (ref "P2_C5") (pin "3") (pinfunction "3_3") (pintype "passive"))
      (node (ref "S_2_C5") (pin "3") (pinfunction "NO2_3") (pintype "passive"))
    )
    (net (code "124") (name "/TDI_2_C6") (class "Default")
      (node (ref "P2_C6") (pin "3") (pinfunction "3_3") (pintype "passive"))
      (node (ref "S_2_C6") (pin "3") (pinfunction "NO2_3") (pintype "passive"))
    )
    (net (code "125") (name "/TDI_3_C1") (class "Default")
      (node (ref "P3_C1") (pin "3") (pinfunction "3_3") (pintype "passive"))
      (node (ref "S_3_C1") (pin "3") (pinfunction "NO2_3") (pintype "passive"))
    )
    (net (code "126") (name "/TDI_3_C2") (class "Default")
      (node (ref "P3_C2") (pin "3") (pinfunction "3_3") (pintype "passive"))
      (node (ref "S_3_C2") (pin "3") (pinfunction "NO2_3") (pintype "passive"))
    )
    (net (code "127") (name "/TDI_3_C3") (class "Default")
      (node (ref "P3_C3") (pin "3") (pinfunction "3_3") (pintype "passive"))
      (node (ref "S_3_C3") (pin "3") (pinfunction "NO2_3") (pintype "passive"))
    )
    (net (code "128") (name "/TDI_3_C4") (class "Default")
      (node (ref "P3_C4") (pin "3") (pinfunction "3_3") (pintype "passive"))
      (node (ref "S_3_C4") (pin "3") (pinfunction "NO2_3") (pintype "passive"))
    )
    (net (code "129") (name "/TDI_3_C5") (class "Default")
      (node (ref "P3_C5") (pin "3") (pinfunction "3_3") (pintype "passive"))
      (node (ref "S_3_C5") (pin "3") (pinfunction "NO2_3") (pintype "passive"))
    )
    (net (code "130") (name "/TDI_3_C6") (class "Default")
      (node (ref "P3_C6") (pin "3") (pinfunction "3_3") (pintype "passive"))
      (node (ref "S_3_C6") (pin "3") (pinfunction "NO2_3") (pintype "passive"))
    )
    (net (code "131") (name "/TDI_4_C1") (class "Default")
      (node (ref "P4_C1") (pin "3") (pinfunction "3_3") (pintype "passive"))
      (node (ref "S_4_C1") (pin "3") (pinfunction "NO2_3") (pintype "passive"))
    )
    (net (code "132") (name "/TDI_4_C2") (class "Default")
      (node (ref "P4_C2") (pin "3") (pinfunction "3_3") (pintype "passive"))
      (node (ref "S_4_C2") (pin "3") (pinfunction "NO2_3") (pintype "passive"))
    )
    (net (code "133") (name "/TDI_4_C3") (class "Default")
      (node (ref "P4_C3") (pin "3") (pinfunction "3_3") (pintype "passive"))
      (node (ref "S_4_C3") (pin "3") (pinfunction "NO2_3") (pintype "passive"))
    )
    (net (code "134") (name "/TDI_4_C4") (class "Default")
      (node (ref "P4_C4") (pin "3") (pinfunction "3_3") (pintype "passive"))
      (node (ref "S_4_C4") (pin "3") (pinfunction "NO2_3") (pintype "passive"))
    )
    (net (code "135") (name "/TDI_4_C5") (class "Default")
      (node (ref "P4_C5") (pin "3") (pinfunction "3_3") (pintype "passive"))
      (node (ref "S_4_C5") (pin "3") (pinfunction "NO2_3") (pintype "passive"))
    )
    (net (code "136") (name "/TDI_4_C6") (class "Default")
      (node (ref "P4_C6") (pin "3") (pinfunction "3_3") (pintype "passive"))
      (node (ref "S_4_C6") (pin "3") (pinfunction "NO2_3") (pintype "passive"))
    )
    (net (code "137") (name "/TDO_1_C1") (class "Default")
      (node (ref "P1_C1") (pin "2") (pinfunction "2_2") (pintype "passive"))
      (node (ref "S_1_C1") (pin "15") (pinfunction "NO1_15") (pintype "passive"))
    )
    (net (code "138") (name "/TDO_1_C2") (class "Default")
      (node (ref "P1_C2") (pin "2") (pinfunction "2_2") (pintype "passive"))
      (node (ref "S_1_C2") (pin "15") (pinfunction "NO1_15") (pintype "passive"))
    )
    (net (code "139") (name "/TDO_1_C3") (class "Default")
      (node (ref "P1_C3") (pin "2") (pinfunction "2_2") (pintype "passive"))
      (node (ref "S_1_C3") (pin "15") (pinfunction "NO1_15") (pintype "passive"))
    )
    (net (code "140") (name "/TDO_1_C4") (class "Default")
      (node (ref "P1_C4") (pin "2") (pinfunction "2_2") (pintype "passive"))
      (node (ref "S_1_C4") (pin "15") (pinfunction "NO1_15") (pintype "passive"))
    )
    (net (code "141") (name "/TDO_1_C5") (class "Default")
      (node (ref "P1_C5") (pin "2") (pinfunction "2_2") (pintype "passive"))
      (node (ref "S_1_C5") (pin "15") (pinfunction "NO1_15") (pintype "passive"))
    )
    (net (code "142") (name "/TDO_1_C6") (class "Default")
      (node (ref "P1_C6") (pin "2") (pinfunction "2_2") (pintype "passive"))
      (node (ref "S_1_C6") (pin "15") (pinfunction "NO1_15") (pintype "passive"))
    )
    (net (code "143") (name "/TDO_2_C1") (class "Default")
      (node (ref "P2_C1") (pin "2") (pinfunction "2_2") (pintype "passive"))
      (node (ref "S_2_C1") (pin "15") (pinfunction "NO1_15") (pintype "passive"))
    )
    (net (code "144") (name "/TDO_2_C2") (class "Default")
      (node (ref "P2_C2") (pin "2") (pinfunction "2_2") (pintype "passive"))
      (node (ref "S_2_C2") (pin "15") (pinfunction "NO1_15") (pintype "passive"))
    )
    (net (code "145") (name "/TDO_2_C3") (class "Default")
      (node (ref "P2_C3") (pin "2") (pinfunction "2_2") (pintype "passive"))
      (node (ref "S_2_C3") (pin "15") (pinfunction "NO1_15") (pintype "passive"))
    )
    (net (code "146") (name "/TDO_2_C4") (class "Default")
      (node (ref "P2_C4") (pin "2") (pinfunction "2_2") (pintype "passive"))
      (node (ref "S_2_C4") (pin "15") (pinfunction "NO1_15") (pintype "passive"))
    )
    (net (code "147") (name "/TDO_2_C5") (class "Default")
      (node (ref "P2_C5") (pin "2") (pinfunction "2_2") (pintype "passive"))
      (node (ref "S_2_C5") (pin "15") (pinfunction "NO1_15") (pintype "passive"))
    )
    (net (code "148") (name "/TDO_2_C6") (class "Default")
      (node (ref "P2_C6") (pin "2") (pinfunction "2_2") (pintype "passive"))
      (node (ref "S_2_C6") (pin "15") (pinfunction "NO1_15") (pintype "passive"))
    )
    (net (code "149") (name "/TDO_3_C1") (class "Default")
      (node (ref "P3_C1") (pin "2") (pinfunction "2_2") (pintype "passive"))
      (node (ref "S_3_C1") (pin "15") (pinfunction "NO1_15") (pintype "passive"))
    )
    (net (code "150") (name "/TDO_3_C2") (class "Default")
      (node (ref "P3_C2") (pin "2") (pinfunction "2_2") (pintype "passive"))
      (node (ref "S_3_C2") (pin "15") (pinfunction "NO1_15") (pintype "passive"))
    )
    (net (code "151") (name "/TDO_3_C3") (class "Default")
      (node (ref "P3_C3") (pin "2") (pinfunction "2_2") (pintype "passive"))
      (node (ref "S_3_C3") (pin "15") (pinfunction "NO1_15") (pintype "passive"))
    )
    (net (code "152") (name "/TDO_3_C4") (class "Default")
      (node (ref "P3_C4") (pin "2") (pinfunction "2_2") (pintype "passive"))
      (node (ref "S_3_C4") (pin "15") (pinfunction "NO1_15") (pintype "passive"))
    )
    (net (code "153") (name "/TDO_3_C5") (class "Default")
      (node (ref "P3_C5") (pin "2") (pinfunction "2_2") (pintype "passive"))
      (node (ref "S_3_C5") (pin "15") (pinfunction "NO1_15") (pintype "passive"))
    )
    (net (code "154") (name "/TDO_3_C6") (class "Default")
      (node (ref "P3_C6") (pin "2") (pinfunction "2_2") (pintype "passive"))
      (node (ref "S_3_C6") (pin "15") (pinfunction "NO1_15") (pintype "passive"))
    )
    (net (code "155") (name "/TDO_4_C1") (class "Default")
      (node (ref "P4_C1") (pin "2") (pinfunction "2_2") (pintype "passive"))
      (node (ref "S_4_C1") (pin "15") (pinfunction "NO1_15") (pintype "passive"))
    )
    (net (code "156") (name "/TDO_4_C2") (class "Default")
      (node (ref "P4_C2") (pin "2") (pinfunction "2_2") (pintype "passive"))
      (node (ref "S_4_C2") (pin "15") (pinfunction "NO1_15") (pintype "passive"))
    )
    (net (code "157") (name "/TDO_4_C3") (class "Default")
      (node (ref "P4_C3") (pin "2") (pinfunction "2_2") (pintype "passive"))
      (node (ref "S_4_C3") (pin "15") (pinfunction "NO1_15") (pintype "passive"))
    )
    (net (code "158") (name "/TDO_4_C4") (class "Default")
      (node (ref "P4_C4") (pin "2") (pinfunction "2_2") (pintype "passive"))
      (node (ref "S_4_C4") (pin "15") (pinfunction "NO1_15") (pintype "passive"))
    )
    (net (code "159") (name "/TDO_4_C5") (class "Default")
      (node (ref "P4_C5") (pin "2") (pinfunction "2_2") (pintype "passive"))
      (node (ref "S_4_C5") (pin "15") (pinfunction "NO1_15") (pintype "passive"))
    )
    (net (code "160") (name "/TDO_4_C6") (class "Default")
      (node (ref "P4_C6") (pin "2") (pinfunction "2_2") (pintype "passive"))
      (node (ref "S_4_C6") (pin "15") (pinfunction "NO1_15") (pintype "passive"))
    )
    (net (code "161") (name "/TMS_1_C1") (class "Default")
      (node (ref "P1_C1") (pin "5") (pinfunction "5_5") (pintype "passive"))
      (node (ref "S_1_C1") (pin "11") (pinfunction "NO4_11") (pintype "passive"))
    )
    (net (code "162") (name "/TMS_1_C2") (class "Default")
      (node (ref "P1_C2") (pin "5") (pinfunction "5_5") (pintype "passive"))
      (node (ref "S_1_C2") (pin "11") (pinfunction "NO4_11") (pintype "passive"))
    )
    (net (code "163") (name "/TMS_1_C3") (class "Default")
      (node (ref "P1_C3") (pin "5") (pinfunction "5_5") (pintype "passive"))
      (node (ref "S_1_C3") (pin "11") (pinfunction "NO4_11") (pintype "passive"))
    )
    (net (code "164") (name "/TMS_1_C4") (class "Default")
      (node (ref "P1_C4") (pin "5") (pinfunction "5_5") (pintype "passive"))
      (node (ref "S_1_C4") (pin "11") (pinfunction "NO4_11") (pintype "passive"))
    )
    (net (code "165") (name "/TMS_1_C5") (class "Default")
      (node (ref "P1_C5") (pin "5") (pinfunction "5_5") (pintype "passive"))
      (node (ref "S_1_C5") (pin "11") (pinfunction "NO4_11") (pintype "passive"))
    )
    (net (code "166") (name "/TMS_1_C6") (class "Default")
      (node (ref "P1_C6") (pin "5") (pinfunction "5_5") (pintype "passive"))
      (node (ref "S_1_C6") (pin "11") (pinfunction "NO4_11") (pintype "passive"))
    )
    (net (code "167") (name "/TMS_2_C1") (class "Default")
      (node (ref "P2_C1") (pin "5") (pinfunction "5_5") (pintype "passive"))
      (node (ref "S_2_C1") (pin "11") (pinfunction "NO4_11") (pintype "passive"))
    )
    (net (code "168") (name "/TMS_2_C2") (class "Default")
      (node (ref "P2_C2") (pin "5") (pinfunction "5_5") (pintype "passive"))
      (node (ref "S_2_C2") (pin "11") (pinfunction "NO4_11") (pintype "passive"))
    )
    (net (code "169") (name "/TMS_2_C3") (class "Default")
      (node (ref "P2_C3") (pin "5") (pinfunction "5_5") (pintype "passive"))
      (node (ref "S_2_C3") (pin "11") (pinfunction "NO4_11") (pintype "passive"))
    )
    (net (code "170") (name "/TMS_2_C4") (class "Default")
      (node (ref "P2_C4") (pin "5") (pinfunction "5_5") (pintype "passive"))
      (node (ref "S_2_C4") (pin "11") (pinfunction "NO4_11") (pintype "passive"))
    )
    (net (code "171") (name "/TMS_2_C5") (class "Default")
      (node (ref "P2_C5") (pin "5") (pinfunction "5_5") (pintype "passive"))
      (node (ref "S_2_C5") (pin "11") (pinfunction "NO4_11") (pintype "passive"))
    )
    (net (code "172") (name "/TMS_2_C6") (class "Default")
      (node (ref "P2_C6") (pin "5") (pinfunction "5_5") (pintype "passive"))
      (node (ref "S_2_C6") (pin "11") (pinfunction "NO4_11") (pintype "passive"))
    )
    (net (code "173") (name "/TMS_3_C1") (class "Default")
      (node (ref "P3_C1") (pin "5") (pinfunction "5_5") (pintype "passive"))
      (node (ref "S_3_C1") (pin "11") (pinfunction "NO4_11") (pintype "passive"))
    )
    (net (code "174") (name "/TMS_3_C2") (class "Default")
      (node (ref "P3_C2") (pin "5") (pinfunction "5_5") (pintype "passive"))
      (node (ref "S_3_C2") (pin "11") (pinfunction "NO4_11") (pintype "passive"))
    )
    (net (code "175") (name "/TMS_3_C3") (class "Default")
      (node (ref "P3_C3") (pin "5") (pinfunction "5_5") (pintype "passive"))
      (node (ref "S_3_C3") (pin "11") (pinfunction "NO4_11") (pintype "passive"))
    )
    (net (code "176") (name "/TMS_3_C4") (class "Default")
      (node (ref "P3_C4") (pin "5") (pinfunction "5_5") (pintype "passive"))
      (node (ref "S_3_C4") (pin "11") (pinfunction "NO4_11") (pintype "passive"))
    )
    (net (code "177") (name "/TMS_3_C5") (class "Default")
      (node (ref "P3_C5") (pin "5") (pinfunction "5_5") (pintype "passive"))
      (node (ref "S_3_C5") (pin "11") (pinfunction "NO4_11") (pintype "passive"))
    )
    (net (code "178") (name "/TMS_3_C6") (class "Default")
      (node (ref "P3_C6") (pin "5") (pinfunction "5_5") (pintype "passive"))
      (node (ref "S_3_C6") (pin "11") (pinfunction "NO4_11") (pintype "passive"))
    )
    (net (code "179") (name "/TMS_4_C1") (class "Default")
      (node (ref "P4_C1") (pin "5") (pinfunction "5_5") (pintype "passive"))
      (node (ref "S_4_C1") (pin "11") (pinfunction "NO4_11") (pintype "passive"))
    )
    (net (code "180") (name "/TMS_4_C2") (class "Default")
      (node (ref "P4_C2") (pin "5") (pinfunction "5_5") (pintype "passive"))
      (node (ref "S_4_C2") (pin "11") (pinfunction "NO4_11") (pintype "passive"))
    )
    (net (code "181") (name "/TMS_4_C3") (class "Default")
      (node (ref "P4_C3") (pin "5") (pinfunction "5_5") (pintype "passive"))
      (node (ref "S_4_C3") (pin "11") (pinfunction "NO4_11") (pintype "passive"))
    )
    (net (code "182") (name "/TMS_4_C4") (class "Default")
      (node (ref "P4_C4") (pin "5") (pinfunction "5_5") (pintype "passive"))
      (node (ref "S_4_C4") (pin "11") (pinfunction "NO4_11") (pintype "passive"))
    )
    (net (code "183") (name "/TMS_4_C5") (class "Default")
      (node (ref "P4_C5") (pin "5") (pinfunction "5_5") (pintype "passive"))
      (node (ref "S_4_C5") (pin "11") (pinfunction "NO4_11") (pintype "passive"))
    )
    (net (code "184") (name "/TMS_4_C6") (class "Default")
      (node (ref "P4_C6") (pin "5") (pinfunction "5_5") (pintype "passive"))
      (node (ref "S_4_C6") (pin "11") (pinfunction "NO4_11") (pintype "passive"))
    )
    (net (code "185") (name "3.3V") (class "Default")
      (node (ref "C10") (pin "1") (pinfunction "1_1") (pintype "passive"))
      (node (ref "C16") (pin "1") (pinfunction "1_1") (pintype "passive"))
      (node (ref "C30") (pin "1") (pinfunction "1_1") (pintype "passive"))
      (node (ref "C41") (pin "1") (pinfunction "1_1") (pintype "passive"))
      (node (ref "C42") (pin "1") (pinfunction "1_1") (pintype "passive"))
      (node (ref "C43") (pin "1") (pinfunction "1_1") (pintype "passive"))
      (node (ref "C6") (pin "1") (pinfunction "1_1") (pintype "passive"))
      (node (ref "C7") (pin "1") (pinfunction "1_1") (pintype "passive"))
      (node (ref "C8") (pin "1") (pinfunction "1_1") (pintype "passive"))
      (node (ref "C9") (pin "1") (pinfunction "1_1") (pintype "passive"))
      (node (ref "LS1") (pin "1") (pinfunction "1_1") (pintype "passive"))
      (node (ref "P17") (pin "1") (pinfunction "1_1") (pintype "passive"))
      (node (ref "P18") (pin "1") (pinfunction "1_1") (pintype "passive"))
      (node (ref "R12") (pin "2") (pinfunction "2_2") (pintype "passive"))
      (node (ref "R15") (pin "2") (pinfunction "2_2") (pintype "passive"))
      (node (ref "R3") (pin "1") (pinfunction "1_1") (pintype "passive"))
      (node (ref "R67") (pin "1") (pinfunction "1_1") (pintype "passive"))
      (node (ref "R68") (pin "1") (pinfunction "1_1") (pintype "passive"))
      (node (ref "R69") (pin "1") (pinfunction "1_1") (pintype "passive"))
      (node (ref "S1") (pin "1") (pinfunction "1_1") (pintype "passive"))
      (node (ref "S1") (pin "2") (pinfunction "2_2") (pintype "passive"))
      (node (ref "S2") (pin "1") (pinfunction "1_1") (pintype "passive"))
      (node (ref "S2") (pin "2") (pinfunction "2_2") (pintype "passive"))
      (node (ref "S_1_C1") (pin "14") (pinfunction "V+_14") (pintype "passive"))
      (node (ref "S_1_C2") (pin "14") (pinfunction "V+_14") (pintype "passive"))
      (node (ref "S_1_C3") (pin "14") (pinfunction "V+_14") (pintype "passive"))
      (node (ref "S_1_C4") (pin "14") (pinfunction "V+_14") (pintype "passive"))
      (node (ref "S_1_C5") (pin "14") (pinfunction "V+_14") (pintype "passive"))
      (node (ref "S_1_C6") (pin "14") (pinfunction "V+_14") (pintype "passive"))
      (node (ref "S_2_C1") (pin "14") (pinfunction "V+_14") (pintype "passive"))
      (node (ref "S_2_C2") (pin "14") (pinfunction "V+_14") (pintype "passive"))
      (node (ref "S_2_C3") (pin "14") (pinfunction "V+_14") (pintype "passive"))
      (node (ref "S_2_C4") (pin "14") (pinfunction "V+_14") (pintype "passive"))
      (node (ref "S_2_C5") (pin "14") (pinfunction "V+_14") (pintype "passive"))
      (node (ref "S_2_C6") (pin "14") (pinfunction "V+_14") (pintype "passive"))
      (node (ref "S_3_C1") (pin "14") (pinfunction "V+_14") (pintype "passive"))
      (node (ref "S_3_C2") (pin "14") (pinfunction "V+_14") (pintype "passive"))
      (node (ref "S_3_C3") (pin "14") (pinfunction "V+_14") (pintype "passive"))
      (node (ref "S_3_C4") (pin "14") (pinfunction "V+_14") (pintype "passive"))
      (node (ref "S_3_C5") (pin "14") (pinfunction "V+_14") (pintype "passive"))
      (node (ref "S_3_C6") (pin "14") (pinfunction "V+_14") (pintype "passive"))
      (node (ref "S_4_C1") (pin "14") (pinfunction "V+_14") (pintype "passive"))
      (node (ref "S_4_C2") (pin "14") (pinfunction "V+_14") (pintype "passive"))
      (node (ref "S_4_C3") (pin "14") (pinfunction "V+_14") (pintype "passive"))
      (node (ref "S_4_C4") (pin "14") (pinfunction "V+_14") (pintype "passive"))
      (node (ref "S_4_C5") (pin "14") (pinfunction "V+_14") (pintype "passive"))
      (node (ref "S_4_C6") (pin "14") (pinfunction "V+_14") (pintype "passive"))
      (node (ref "U14") (pin "16") (pinfunction "VCC_16") (pintype "passive"))
      (node (ref "U15") (pin "16") (pinfunction "VCC_16") (pintype "passive"))
      (node (ref "U3") (pin "5") (pinfunction "5_5") (pintype "passive"))
      (node (ref "U4") (pin "3") (pinfunction "VOUT_3") (pintype "passive"))
      (node (ref "U5") (pin "16") (pinfunction "VCC_16") (pintype "passive"))
      (node (ref "U6") (pin "1") (pinfunction "VBAT_1") (pintype "power_in"))
      (node (ref "U6") (pin "24") (pinfunction "VDD_1_24") (pintype "power_in"))
      (node (ref "U6") (pin "36") (pinfunction "VDD_2_36") (pintype "power_in"))
      (node (ref "U6") (pin "48") (pinfunction "VDD_3_48") (pintype "power_in"))
    )
    (net (code "186") (name "8V") (class "Default")
      (node (ref "C52") (pin "1") (pinfunction "1_1") (pintype "passive"))
      (node (ref "C53") (pin "1") (pinfunction "1_1") (pintype "passive"))
      (node (ref "D4") (pin "1") (pinfunction "A_1") (pintype "passive"))
      (node (ref "D5") (pin "1") (pinfunction "A_1") (pintype "passive"))
      (node (ref "L4") (pin "2") (pinfunction "2_2") (pintype "passive"))
      (node (ref "P23") (pin "1") (pinfunction "1_1") (pintype "passive"))
      (node (ref "R8") (pin "2") (pinfunction "2_2") (pintype "passive"))
    )
    (net (code "187") (name "12V") (class "Default")
      (node (ref "C2") (pin "1") (pinfunction "1_1") (pintype "passive"))
      (node (ref "C3") (pin "1") (pinfunction "1_1") (pintype "passive"))
      (node (ref "C4") (pin "1") (pinfunction "1_1") (pintype "passive"))
      (node (ref "C48") (pin "1") (pinfunction "1_1") (pintype "passive"))
      (node (ref "L1") (pin "1") (pinfunction "1_1") (pintype "passive"))
      (node (ref "R6") (pin "2") (pinfunction "2_2") (pintype "passive"))
      (node (ref "U2") (pin "2") (pinfunction "IN_2") (pintype "passive"))
    )
    (net (code "188") (name "GND") (class "Default")
      (node (ref "C10") (pin "2") (pinfunction "2_2") (pintype "passive"))
      (node (ref "C15") (pin "2") (pinfunction "2_2") (pintype "passive"))
      (node (ref "C16") (pin "2") (pinfunction "2_2") (pintype "passive"))
      (node (ref "C2") (pin "2") (pinfunction "2_2") (pintype "passive"))
      (node (ref "C21") (pin "2") (pinfunction "2_2") (pintype "passive"))
      (node (ref "C22") (pin "2") (pinfunction "2_2") (pintype "passive"))
      (node (ref "C23") (pin "1") (pinfunction "1_1") (pintype "passive"))
      (node (ref "C24") (pin "2") (pinfunction "2_2") (pintype "passive"))
      (node (ref "C25") (pin "2") (pinfunction "2_2") (pintype "passive"))
      (node (ref "C26") (pin "2") (pinfunction "2_2") (pintype "passive"))
      (node (ref "C27") (pin "2") (pinfunction "2_2") (pintype "passive"))
      (node (ref "C3") (pin "2") (pinfunction "2_2") (pintype "passive"))
      (node (ref "C30") (pin "2") (pinfunction "2_2") (pintype "passive"))
      (node (ref "C38") (pin "1") (pinfunction "1_1") (pintype "passive"))
      (node (ref "C39") (pin "1") (pinfunction "1_1") (pintype "passive"))
      (node (ref "C4") (pin "2") (pinfunction "2_2") (pintype "passive"))
      (node (ref "C41") (pin "2") (pinfunction "2_2") (pintype "passive"))
      (node (ref "C42") (pin "2") (pinfunction "2_2") (pintype "passive"))
      (node (ref "C43") (pin "2") (pinfunction "2_2") (pintype "passive"))
      (node (ref "C48") (pin "2") (pinfunction "2_2") (pintype "passive"))
      (node (ref "C5") (pin "2") (pinfunction "2_2") (pintype "passive"))
      (node (ref "C50") (pin "2") (pinfunction "2_2") (pintype "passive"))
      (node (ref "C52") (pin "2") (pinfunction "2_2") (pintype "passive"))
      (node (ref "C53") (pin "2") (pinfunction "2_2") (pintype "passive"))
      (node (ref "C6") (pin "2") (pinfunction "2_2") (pintype "passive"))
      (node (ref "C7") (pin "2") (pinfunction "2_2") (pintype "passive"))
      (node (ref "C8") (pin "2") (pinfunction "2_2") (pintype "passive"))
      (node (ref "C9") (pin "2") (pinfunction "2_2") (pintype "passive"))
      (node (ref "D8") (pin "1") (pinfunction "A_1") (pintype "passive"))
      (node (ref "J1") (pin "5") (pinfunction "5_5") (pintype "passive"))
      (node (ref "JTAG") (pin "6") (pinfunction "GND_6") (pintype "passive"))
      (node (ref "L2") (pin "1") (pinfunction "1_1") (pintype "passive"))
      (node (ref "LD0") (pin "2") (pinfunction "K_2") (pintype "passive"))
      (node (ref "P17") (pin "2") (pinfunction "2_2") (pintype "passive"))
      (node (ref "P18") (pin "2") (pinfunction "2_2") (pintype "passive"))
      (node (ref "P1_C1") (pin "6") (pinfunction "6_6") (pintype "passive"))
      (node (ref "P1_C2") (pin "6") (pinfunction "6_6") (pintype "passive"))
      (node (ref "P1_C3") (pin "6") (pinfunction "6_6") (pintype "passive"))
      (node (ref "P1_C4") (pin "6") (pinfunction "6_6") (pintype "passive"))
      (node (ref "P1_C5") (pin "6") (pinfunction "6_6") (pintype "passive"))
      (node (ref "P1_C6") (pin "6") (pinfunction "6_6") (pintype "passive"))
      (node (ref "P23") (pin "5") (pinfunction "5_5") (pintype "passive"))
      (node (ref "P24") (pin "4") (pinfunction "4_4") (pintype "passive"))
      (node (ref "P2_C1") (pin "6") (pinfunction "6_6") (pintype "passive"))
      (node (ref "P2_C2") (pin "6") (pinfunction "6_6") (pintype "passive"))
      (node (ref "P2_C3") (pin "6") (pinfunction "6_6") (pintype "passive"))
      (node (ref "P2_C4") (pin "6") (pinfunction "6_6") (pintype "passive"))
      (node (ref "P2_C5") (pin "6") (pinfunction "6_6") (pintype "passive"))
      (node (ref "P2_C6") (pin "6") (pinfunction "6_6") (pintype "passive"))
      (node (ref "P3_C1") (pin "6") (pinfunction "6_6") (pintype "passive"))
      (node (ref "P3_C2") (pin "6") (pinfunction "6_6") (pintype "passive"))
      (node (ref "P3_C3") (pin "6") (pinfunction "6_6") (pintype "passive"))
      (node (ref "P3_C4") (pin "6") (pinfunction "6_6") (pintype "passive"))
      (node (ref "P3_C5") (pin "6") (pinfunction "6_6") (pintype "passive"))
      (node (ref "P3_C6") (pin "6") (pinfunction "6_6") (pintype "passive"))
      (node (ref "P4_C1") (pin "6") (pinfunction "6_6") (pintype "passive"))
      (node (ref "P4_C2") (pin "6") (pinfunction "6_6") (pintype "passive"))
      (node (ref "P4_C3") (pin "6") (pinfunction "6_6") (pintype "passive"))
      (node (ref "P4_C4") (pin "6") (pinfunction "6_6") (pintype "passive"))
      (node (ref "P4_C5") (pin "6") (pinfunction "6_6") (pintype "passive"))
      (node (ref "P4_C6") (pin "6") (pinfunction "6_6") (pintype "passive"))
      (node (ref "P_1_C1") (pin "2") (pinfunction "GND_2") (pintype "passive"))
      (node (ref "P_1_C2") (pin "2") (pinfunction "GND_2") (pintype "passive"))
      (node (ref "P_1_C3") (pin "2") (pinfunction "GND_2") (pintype "passive"))
      (node (ref "P_1_C4") (pin "2") (pinfunction "GND_2") (pintype "passive"))
      (node (ref "P_1_C5") (pin "2") (pinfunction "GND_2") (pintype "passive"))
      (node (ref "P_1_C6") (pin "2") (pinfunction "GND_2") (pintype "passive"))
      (node (ref "P_2_C1") (pin "2") (pinfunction "GND_2") (pintype "passive"))
      (node (ref "P_2_C2") (pin "2") (pinfunction "GND_2") (pintype "passive"))
      (node (ref "P_2_C3") (pin "2") (pinfunction "GND_2") (pintype "passive"))
      (node (ref "P_2_C4") (pin "2") (pinfunction "GND_2") (pintype "passive"))
      (node (ref "P_2_C5") (pin "2") (pinfunction "GND_2") (pintype "passive"))
      (node (ref "P_2_C6") (pin "2") (pinfunction "GND_2") (pintype "passive"))
      (node (ref "P_3_C1") (pin "2") (pinfunction "GND_2") (pintype "passive"))
      (node (ref "P_3_C2") (pin "2") (pinfunction "GND_2") (pintype "passive"))
      (node (ref "P_3_C3") (pin "2") (pinfunction "GND_2") (pintype "passive"))
      (node (ref "P_3_C4") (pin "2") (pinfunction "GND_2") (pintype "passive"))
      (node (ref "P_3_C5") (pin "2") (pinfunction "GND_2") (pintype "passive"))
      (node (ref "P_3_C6") (pin "2") (pinfunction "GND_2") (pintype "passive"))
      (node (ref "P_4_C1") (pin "2") (pinfunction "GND_2") (pintype "passive"))
      (node (ref "P_4_C2") (pin "2") (pinfunction "GND_2") (pintype "passive"))
      (node (ref "P_4_C3") (pin "2") (pinfunction "GND_2") (pintype "passive"))
      (node (ref "P_4_C4") (pin "2") (pinfunction "GND_2") (pintype "passive"))
      (node (ref "P_4_C5") (pin "2") (pinfunction "GND_2") (pintype "passive"))
      (node (ref "P_4_C6") (pin "2") (pinfunction "GND_2") (pintype "passive"))
      (node (ref "Q7") (pin "2") (pinfunction "E_2") (pintype "passive"))
      (node (ref "R10") (pin "1") (pinfunction "1_1") (pintype "passive"))
      (node (ref "R14") (pin "1") (pinfunction "1_1") (pintype "passive"))
      (node (ref "R17") (pin "1") (pinfunction "1_1") (pintype "passive"))
      (node (ref "R21") (pin "1") (pinfunction "1_1") (pintype "passive"))
      (node (ref "R29") (pin "2") (pinfunction "2_2") (pintype "passive"))
      (node (ref "R30") (pin "2") (pinfunction "2_2") (pintype "passive"))
      (node (ref "R31") (pin "2") (pinfunction "2_2") (pintype "passive"))
      (node (ref "R32") (pin "2") (pinfunction "2_2") (pintype "passive"))
      (node (ref "R33") (pin "2") (pinfunction "2_2") (pintype "passive"))
      (node (ref "R34") (pin "2") (pinfunction "2_2") (pintype "passive"))
      (node (ref "R40") (pin "2") (pinfunction "2_2") (pintype "passive"))
      (node (ref "R41") (pin "2") (pinfunction "2_2") (pintype "passive"))
      (node (ref "R45") (pin "1") (pinfunction "1_1") (pintype "passive"))
      (node (ref "R48") (pin "1") (pinfunction "1_1") (pintype "passive"))
      (node (ref "R52") (pin "2") (pinfunction "2_2") (pintype "passive"))
      (node (ref "R53") (pin "2") (pinfunction "2_2") (pintype "passive"))
      (node (ref "R54") (pin "2") (pinfunction "2_2") (pintype "passive"))
      (node (ref "R55") (pin "2") (pinfunction "2_2") (pintype "passive"))
      (node (ref "R56") (pin "2") (pinfunction "2_2") (pintype "passive"))
      (node (ref "R57") (pin "2") (pinfunction "2_2") (pintype "passive"))
      (node (ref "R61") (pin "2") (pinfunction "2_2") (pintype "passive"))
      (node (ref "R62") (pin "2") (pinfunction "2_2") (pintype "passive"))
      (node (ref "R63") (pin "2") (pinfunction "2_2") (pintype "passive"))
      (node (ref "R64") (pin "2") (pinfunction "2_2") (pintype "passive"))
      (node (ref "R65") (pin "2") (pinfunction "2_2") (pintype "passive"))
      (node (ref "R66") (pin "2") (pinfunction "2_2") (pintype "passive"))
      (node (ref "R7") (pin "1") (pinfunction "1_1") (pintype "passive"))
      (node (ref "R71") (pin "2") (pinfunction "2_2") (pintype "passive"))
      (node (ref "R72") (pin "2") (pinfunction "2_2") (pintype "passive"))
      (node (ref "R73") (pin "2") (pinfunction "2_2") (pintype "passive"))
      (node (ref "R74") (pin "2") (pinfunction "2_2") (pintype "passive"))
      (node (ref "R75") (pin "2") (pinfunction "2_2") (pintype "passive"))
      (node (ref "R76") (pin "2") (pinfunction "2_2") (pintype "passive"))
      (node (ref "S0") (pin "3") (pinfunction "3_3") (pintype "passive"))
      (node (ref "S0") (pin "4") (pinfunction "4_4") (pintype "passive"))
      (node (ref "S_1_C1") (pin "17") (pinfunction "GND_17") (pintype "passive"))
      (node (ref "S_1_C1") (pin "6") (pinfunction "GND_6") (pintype "passive"))
      (node (ref "S_1_C2") (pin "17") (pinfunction "GND_17") (pintype "passive"))
      (node (ref "S_1_C2") (pin "6") (pinfunction "GND_6") (pintype "passive"))
      (node (ref "S_1_C3") (pin "17") (pinfunction "GND_17") (pintype "passive"))
      (node (ref "S_1_C3") (pin "6") (pinfunction "GND_6") (pintype "passive"))
      (node (ref "S_1_C4") (pin "17") (pinfunction "GND_17") (pintype "passive"))
      (node (ref "S_1_C4") (pin "6") (pinfunction "GND_6") (pintype "passive"))
      (node (ref "S_1_C5") (pin "17") (pinfunction "GND_17") (pintype "passive"))
      (node (ref "S_1_C5") (pin "6") (pinfunction "GND_6") (pintype "passive"))
      (node (ref "S_1_C6") (pin "17") (pinfunction "GND_17") (pintype "passive"))
      (node (ref "S_1_C6") (pin "6") (pinfunction "GND_6") (pintype "passive"))
      (node (ref "S_2_C1") (pin "17") (pinfunction "GND_17") (pintype "passive"))
      (node (ref "S_2_C1") (pin "6") (pinfunction "GND_6") (pintype "passive"))
      (node (ref "S_2_C2") (pin "17") (pinfunction "GND_17") (pintype "passive"))
      (node (ref "S_2_C2") (pin "6") (pinfunction "GND_6") (pintype "passive"))
      (node (ref "S_2_C3") (pin "17") (pinfunction "GND_17") (pintype "passive"))
      (node (ref "S_2_C3") (pin "6") (pinfunction "GND_6") (pintype "passive"))
      (node (ref "S_2_C4") (pin "17") (pinfunction "GND_17") (pintype "passive"))
      (node (ref "S_2_C4") (pin "6") (pinfunction "GND_6") (pintype "passive"))
      (node (ref "S_2_C5") (pin "17") (pinfunction "GND_17") (pintype "passive"))
      (node (ref "S_2_C5") (pin "6") (pinfunction "GND_6") (pintype "passive"))
      (node (ref "S_2_C6") (pin "17") (pinfunction "GND_17") (pintype "passive"))
      (node (ref "S_2_C6") (pin "6") (pinfunction "GND_6") (pintype "passive"))
      (node (ref "S_3_C1") (pin "17") (pinfunction "GND_17") (pintype "passive"))
      (node (ref "S_3_C1") (pin "6") (pinfunction "GND_6") (pintype "passive"))
      (node (ref "S_3_C2") (pin "17") (pinfunction "GND_17") (pintype "passive"))
      (node (ref "S_3_C2") (pin "6") (pinfunction "GND_6") (pintype "passive"))
      (node (ref "S_3_C3") (pin "17") (pinfunction "GND_17") (pintype "passive"))
      (node (ref "S_3_C3") (pin "6") (pinfunction "GND_6") (pintype "passive"))
      (node (ref "S_3_C4") (pin "17") (pinfunction "GND_17") (pintype "passive"))
      (node (ref "S_3_C4") (pin "6") (pinfunction "GND_6") (pintype "passive"))
      (node (ref "S_3_C5") (pin "17") (pinfunction "GND_17") (pintype "passive"))
      (node (ref "S_3_C5") (pin "6") (pinfunction "GND_6") (pintype "passive"))
      (node (ref "S_3_C6") (pin "17") (pinfunction "GND_17") (pintype "passive"))
      (node (ref "S_3_C6") (pin "6") (pinfunction "GND_6") (pintype "passive"))
      (node (ref "S_4_C1") (pin "17") (pinfunction "GND_17") (pintype "passive"))
      (node (ref "S_4_C1") (pin "6") (pinfunction "GND_6") (pintype "passive"))
      (node (ref "S_4_C2") (pin "17") (pinfunction "GND_17") (pintype "passive"))
      (node (ref "S_4_C2") (pin "6") (pinfunction "GND_6") (pintype "passive"))
      (node (ref "S_4_C3") (pin "17") (pinfunction "GND_17") (pintype "passive"))
      (node (ref "S_4_C3") (pin "6") (pinfunction "GND_6") (pintype "passive"))
      (node (ref "S_4_C4") (pin "17") (pinfunction "GND_17") (pintype "passive"))
      (node (ref "S_4_C4") (pin "6") (pinfunction "GND_6") (pintype "passive"))
      (node (ref "S_4_C5") (pin "17") (pinfunction "GND_17") (pintype "passive"))
      (node (ref "S_4_C5") (pin "6") (pinfunction "GND_6") (pintype "passive"))
      (node (ref "S_4_C6") (pin "17") (pinfunction "GND_17") (pintype "passive"))
      (node (ref "S_4_C6") (pin "6") (pinfunction "GND_6") (pintype "passive"))
      (node (ref "U14") (pin "13") (pinfunction "/OE_13") (pintype "passive"))
      (node (ref "U14") (pin "8") (pinfunction "GND_8") (pintype "passive"))
      (node (ref "U15") (pin "13") (pinfunction "/OE_13") (pintype "passive"))
      (node (ref "U15") (pin "8") (pinfunction "GND_8") (pintype "passive"))
      (node (ref "U16") (pin "1") (pinfunction "GND_1") (pintype "passive"))
      (node (ref "U2") (pin "4") (pinfunction "GND_4") (pintype "passive"))
      (node (ref "U2") (pin "9") (pinfunction "GND_9") (pintype "passive"))
      (node (ref "U3") (pin "2") (pinfunction "GND_2") (pintype "passive"))
      (node (ref "U4") (pin "1") (pinfunction "GND_1") (pintype "passive"))
      (node (ref "U5") (pin "13") (pinfunction "/OE_13") (pintype "passive"))
      (node (ref "U5") (pin "8") (pinfunction "GND_8") (pintype "passive"))
      (node (ref "U6") (pin "23") (pinfunction "VSS_1_23") (pintype "power_in"))
      (node (ref "U6") (pin "35") (pinfunction "VSS_2_35") (pintype "power_in"))
      (node (ref "U6") (pin "47") (pinfunction "VSS_3_47") (pintype "power_in"))
      (node (ref "U6") (pin "8") (pinfunction "VSSA_8") (pintype "power_in"))
    )
    (net (code "189") (name "JTAG_VDD") (class "Default")
      (node (ref "C15") (pin "1") (pinfunction "1_1") (pintype "passive"))
      (node (ref "JTAG") (pin "1") (pinfunction "JTAG_VDD_1") (pintype "passive"))
      (node (ref "P_1_C1") (pin "5") (pinfunction "VIN_5") (pintype "passive"))
      (node (ref "P_1_C2") (pin "5") (pinfunction "VIN_5") (pintype "passive"))
      (node (ref "P_1_C3") (pin "5") (pinfunction "VIN_5") (pintype "passive"))
      (node (ref "P_1_C4") (pin "5") (pinfunction "VIN_5") (pintype "passive"))
      (node (ref "P_1_C5") (pin "5") (pinfunction "VIN_5") (pintype "passive"))
      (node (ref "P_1_C6") (pin "5") (pinfunction "VIN_5") (pintype "passive"))
      (node (ref "P_2_C1") (pin "5") (pinfunction "VIN_5") (pintype "passive"))
      (node (ref "P_2_C2") (pin "5") (pinfunction "VIN_5") (pintype "passive"))
      (node (ref "P_2_C3") (pin "5") (pinfunction "VIN_5") (pintype "passive"))
      (node (ref "P_2_C4") (pin "5") (pinfunction "VIN_5") (pintype "passive"))
      (node (ref "P_2_C5") (pin "5") (pinfunction "VIN_5") (pintype "passive"))
      (node (ref "P_2_C6") (pin "5") (pinfunction "VIN_5") (pintype "passive"))
      (node (ref "P_3_C1") (pin "5") (pinfunction "VIN_5") (pintype "passive"))
      (node (ref "P_3_C2") (pin "5") (pinfunction "VIN_5") (pintype "passive"))
      (node (ref "P_3_C3") (pin "5") (pinfunction "VIN_5") (pintype "passive"))
      (node (ref "P_3_C4") (pin "5") (pinfunction "VIN_5") (pintype "passive"))
      (node (ref "P_3_C5") (pin "5") (pinfunction "VIN_5") (pintype "passive"))
      (node (ref "P_3_C6") (pin "5") (pinfunction "VIN_5") (pintype "passive"))
      (node (ref "P_4_C1") (pin "5") (pinfunction "VIN_5") (pintype "passive"))
      (node (ref "P_4_C2") (pin "5") (pinfunction "VIN_5") (pintype "passive"))
      (node (ref "P_4_C3") (pin "5") (pinfunction "VIN_5") (pintype "passive"))
      (node (ref "P_4_C4") (pin "5") (pinfunction "VIN_5") (pintype "passive"))
      (node (ref "P_4_C5") (pin "5") (pinfunction "VIN_5") (pintype "passive"))
      (node (ref "P_4_C6") (pin "5") (pinfunction "VIN_5") (pintype "passive"))
    )
    (net (code "190") (name "Net-(C51-Pad2)") (class "Default")
      (node (ref "C51") (pin "2") (pinfunction "2_2") (pintype "passive"))
      (node (ref "R10") (pin "2") (pinfunction "2_2") (pintype "passive"))
    )
    (net (code "191") (name "Net-(D1-A)") (class "Default")
      (node (ref "D1") (pin "1") (pinfunction "A_1") (pintype "passive"))
      (node (ref "P0") (pin "1") (pinfunction "1_1") (pintype "passive"))
    )
    (net (code "192") (name "Net-(D1-K)") (class "Default")
      (node (ref "D1") (pin "2") (pinfunction "K_2") (pintype "passive"))
      (node (ref "F1") (pin "1") (pinfunction "1_1") (pintype "passive"))
    )
    (net (code "193") (name "Net-(D4-K)") (class "Default")
      (node (ref "C21") (pin "1") (pinfunction "1_1") (pintype "passive"))
      (node (ref "D4") (pin "2") (pinfunction "K_2") (pintype "passive"))
      (node (ref "U16") (pin "2") (pinfunction "VIN_2") (pintype "passive"))
    )
    (net (code "194") (name "Net-(D5-K)") (class "Default")
      (node (ref "C5") (pin "1") (pinfunction "1_1") (pintype "passive"))
      (node (ref "D5") (pin "2") (pinfunction "K_2") (pintype "passive"))
      (node (ref "U4") (pin "2") (pinfunction "VIN_2") (pintype "passive"))
    )
    (net (code "195") (name "Net-(D8-K)") (class "Default")
      (node (ref "C49") (pin "1") (pinfunction "1_1") (pintype "passive"))
      (node (ref "D8") (pin "2") (pinfunction "K_2") (pintype "passive"))
      (node (ref "L4") (pin "1") (pinfunction "1_1") (pintype "passive"))
      (node (ref "U2") (pin "3") (pinfunction "SW_3") (pintype "passive"))
    )
    (net (code "196") (name "Net-(J1-Pad3)") (class "Default")
      (node (ref "J1") (pin "3") (pinfunction "3_3") (pintype "passive"))
      (node (ref "R2") (pin "1") (pinfunction "1_1") (pintype "passive"))
    )
    (net (code "197") (name "Net-(J1-Pad7)") (class "Default")
      (node (ref "J1") (pin "7") (pinfunction "7_7") (pintype "passive"))
      (node (ref "R1") (pin "1") (pinfunction "1_1") (pintype "passive"))
    )
    (net (code "198") (name "Net-(J1-Pad8)") (class "Default")
      (node (ref "J1") (pin "8") (pinfunction "8_8") (pintype "passive"))
      (node (ref "R5") (pin "1") (pinfunction "1_1") (pintype "passive"))
    )
    (net (code "199") (name "Net-(J1-Pad9)") (class "Default")
      (node (ref "J1") (pin "9") (pinfunction "9_9") (pintype "passive"))
      (node (ref "R9") (pin "1") (pinfunction "1_1") (pintype "passive"))
    )
    (net (code "200") (name "Net-(LD0-A)") (class "Default")
      (node (ref "LD0") (pin "1") (pinfunction "A_1") (pintype "passive"))
      (node (ref "R3") (pin "2") (pinfunction "2_2") (pintype "passive"))
    )
    (net (code "201") (name "Net-(P23-Pad2)") (class "Default")
      (node (ref "P23") (pin "2") (pinfunction "2_2") (pintype "passive"))
      (node (ref "R43") (pin "1") (pinfunction "1_1") (pintype "passive"))
    )
    (net (code "202") (name "Net-(P_1_C1-ISET)") (class "Default")
      (node (ref "P_1_C1") (pin "3") (pinfunction "ISET_3") (pintype "passive"))
      (node (ref "R29") (pin "1") (pinfunction "1_1") (pintype "passive"))
    )
    (net (code "203") (name "Net-(P_1_C2-ISET)") (class "Default")
      (node (ref "P_1_C2") (pin "3") (pinfunction "ISET_3") (pintype "passive"))
      (node (ref "R30") (pin "1") (pinfunction "1_1") (pintype "passive"))
    )
    (net (code "204") (name "Net-(P_1_C3-ISET)") (class "Default")
      (node (ref "P_1_C3") (pin "3") (pinfunction "ISET_3") (pintype "passive"))
      (node (ref "R31") (pin "1") (pinfunction "1_1") (pintype "passive"))
    )
    (net (code "205") (name "Net-(P_1_C4-ISET)") (class "Default")
      (node (ref "P_1_C4") (pin "3") (pinfunction "ISET_3") (pintype "passive"))
      (node (ref "R32") (pin "1") (pinfunction "1_1") (pintype "passive"))
    )
    (net (code "206") (name "Net-(P_1_C5-ISET)") (class "Default")
      (node (ref "P_1_C5") (pin "3") (pinfunction "ISET_3") (pintype "passive"))
      (node (ref "R33") (pin "1") (pinfunction "1_1") (pintype "passive"))
    )
    (net (code "207") (name "Net-(P_1_C6-ISET)") (class "Default")
      (node (ref "P_1_C6") (pin "3") (pinfunction "ISET_3") (pintype "passive"))
      (node (ref "R34") (pin "1") (pinfunction "1_1") (pintype "passive"))
    )
    (net (code "208") (name "Net-(P_2_C1-ISET)") (class "Default")
      (node (ref "P_2_C1") (pin "3") (pinfunction "ISET_3") (pintype "passive"))
      (node (ref "R57") (pin "1") (pinfunction "1_1") (pintype "passive"))
    )
    (net (code "209") (name "Net-(P_2_C2-ISET)") (class "Default")
      (node (ref "P_2_C2") (pin "3") (pinfunction "ISET_3") (pintype "passive"))
      (node (ref "R52") (pin "1") (pinfunction "1_1") (pintype "passive"))
    )
    (net (code "210") (name "Net-(P_2_C3-ISET)") (class "Default")
      (node (ref "P_2_C3") (pin "3") (pinfunction "ISET_3") (pintype "passive"))
      (node (ref "R53") (pin "1") (pinfunction "1_1") (pintype "passive"))
    )
    (net (code "211") (name "Net-(P_2_C4-ISET)") (class "Default")
      (node (ref "P_2_C4") (pin "3") (pinfunction "ISET_3") (pintype "passive"))
      (node (ref "R54") (pin "1") (pinfunction "1_1") (pintype "passive"))
    )
    (net (code "212") (name "Net-(P_2_C5-ISET)") (class "Default")
      (node (ref "P_2_C5") (pin "3") (pinfunction "ISET_3") (pintype "passive"))
      (node (ref "R55") (pin "1") (pinfunction "1_1") (pintype "passive"))
    )
    (net (code "213") (name "Net-(P_2_C6-ISET)") (class "Default")
      (node (ref "P_2_C6") (pin "3") (pinfunction "ISET_3") (pintype "passive"))
      (node (ref "R56") (pin "1") (pinfunction "1_1") (pintype "passive"))
    )
    (net (code "214") (name "Net-(P_3_C1-ISET)") (class "Default")
      (node (ref "P_3_C1") (pin "3") (pinfunction "ISET_3") (pintype "passive"))
      (node (ref "R61") (pin "1") (pinfunction "1_1") (pintype "passive"))
    )
    (net (code "215") (name "Net-(P_3_C2-ISET)") (class "Default")
      (node (ref "P_3_C2") (pin "3") (pinfunction "ISET_3") (pintype "passive"))
      (node (ref "R62") (pin "1") (pinfunction "1_1") (pintype "passive"))
    )
    (net (code "216") (name "Net-(P_3_C3-ISET)") (class "Default")
      (node (ref "P_3_C3") (pin "3") (pinfunction "ISET_3") (pintype "passive"))
      (node (ref "R63") (pin "1") (pinfunction "1_1") (pintype "passive"))
    )
    (net (code "217") (name "Net-(P_3_C4-ISET)") (class "Default")
      (node (ref "P_3_C4") (pin "3") (pinfunction "ISET_3") (pintype "passive"))
      (node (ref "R64") (pin "1") (pinfunction "1_1") (pintype "passive"))
    )
    (net (code "218") (name "Net-(P_3_C5-ISET)") (class "Default")
      (node (ref "P_3_C5") (pin "3") (pinfunction "ISET_3") (pintype "passive"))
      (node (ref "R65") (pin "1") (pinfunction "1_1") (pintype "passive"))
    )
    (net (code "219") (name "Net-(P_3_C6-ISET)") (class "Default")
      (node (ref "P_3_C6") (pin "3") (pinfunction "ISET_3") (pintype "passive"))
      (node (ref "R66") (pin "1") (pinfunction "1_1") (pintype "passive"))
    )
    (net (code "220") (name "Net-(P_4_C1-ISET)") (class "Default")
      (node (ref "P_4_C1") (pin "3") (pinfunction "ISET_3") (pintype "passive"))
      (node (ref "R71") (pin "1") (pinfunction "1_1") (pintype "passive"))
    )
    (net (code "221") (name "Net-(P_4_C2-ISET)") (class "Default")
      (node (ref "P_4_C2") (pin "3") (pinfunction "ISET_3") (pintype "passive"))
      (node (ref "R72") (pin "1") (pinfunction "1_1") (pintype "passive"))
    )
    (net (code "222") (name "Net-(P_4_C3-ISET)") (class "Default")
      (node (ref "P_4_C3") (pin "3") (pinfunction "ISET_3") (pintype "passive"))
      (node (ref "R73") (pin "1") (pinfunction "1_1") (pintype "passive"))
    )
    (net (code "223") (name "Net-(P_4_C4-ISET)") (class "Default")
      (node (ref "P_4_C4") (pin "3") (pinfunction "ISET_3") (pintype "passive"))
      (node (ref "R74") (pin "1") (pinfunction "1_1") (pintype "passive"))
    )
    (net (code "224") (name "Net-(P_4_C5-ISET)") (class "Default")
      (node (ref "P_4_C5") (pin "3") (pinfunction "ISET_3") (pintype "passive"))
      (node (ref "R75") (pin "1") (pinfunction "1_1") (pintype "passive"))
    )
    (net (code "225") (name "Net-(P_4_C6-ISET)") (class "Default")
      (node (ref "P_4_C6") (pin "3") (pinfunction "ISET_3") (pintype "passive"))
      (node (ref "R76") (pin "1") (pinfunction "1_1") (pintype "passive"))
    )
    (net (code "226") (name "Net-(Q7-B)") (class "Default")
      (node (ref "Q7") (pin "1") (pinfunction "B_1") (pintype "passive"))
      (node (ref "R20") (pin "2") (pinfunction "2_2") (pintype "passive"))
      (node (ref "R21") (pin "2") (pinfunction "2_2") (pintype "passive"))
    )
    (net (code "227") (name "Net-(Q7-C)") (class "Default")
      (node (ref "LS1") (pin "2") (pinfunction "2_2") (pintype "passive"))
      (node (ref "Q7") (pin "3") (pinfunction "C_3") (pintype "passive"))
    )
    (net (code "228") (name "Net-(R36-Pad2)") (class "Default")
      (node (ref "R36") (pin "2") (pinfunction "2_2") (pintype "passive"))
      (node (ref "S1") (pin "3") (pinfunction "3_3") (pintype "passive"))
      (node (ref "S1") (pin "4") (pinfunction "4_4") (pintype "passive"))
    )
    (net (code "229") (name "Net-(R37-Pad2)") (class "Default")
      (node (ref "R37") (pin "2") (pinfunction "2_2") (pintype "passive"))
      (node (ref "S2") (pin "3") (pinfunction "3_3") (pintype "passive"))
      (node (ref "S2") (pin "4") (pinfunction "4_4") (pintype "passive"))
    )
    (net (code "230") (name "Net-(U2-BS)") (class "Default")
      (node (ref "C49") (pin "2") (pinfunction "2_2") (pintype "passive"))
      (node (ref "U2") (pin "1") (pinfunction "BS_1") (pintype "passive"))
    )
    (net (code "231") (name "Net-(U2-COMP)") (class "Default")
      (node (ref "C51") (pin "1") (pinfunction "1_1") (pintype "passive"))
      (node (ref "U2") (pin "6") (pinfunction "COMP_6") (pintype "passive"))
    )
    (net (code "232") (name "Net-(U2-EN)") (class "Default")
      (node (ref "R6") (pin "1") (pinfunction "1_1") (pintype "passive"))
      (node (ref "U2") (pin "7") (pinfunction "EN_7") (pintype "passive"))
    )
    (net (code "233") (name "Net-(U2-FB)") (class "Default")
      (node (ref "R7") (pin "2") (pinfunction "2_2") (pintype "passive"))
      (node (ref "R8") (pin "1") (pinfunction "1_1") (pintype "passive"))
      (node (ref "U2") (pin "5") (pinfunction "FB_5") (pintype "passive"))
    )
    (net (code "234") (name "Net-(U2-SS)") (class "Default")
      (node (ref "C50") (pin "1") (pinfunction "1_1") (pintype "passive"))
      (node (ref "U2") (pin "8") (pinfunction "SS_8") (pintype "passive"))
    )
    (net (code "235") (name "Net-(U5-{slash}SRCLR)") (class "Default")
      (node (ref "R68") (pin "2") (pinfunction "2_2") (pintype "passive"))
      (node (ref "U5") (pin "10") (pinfunction "/SRCLR_10") (pintype "passive"))
    )
    (net (code "236") (name "Net-(U6-VDDA)") (class "Default")
      (node (ref "C27") (pin "1") (pinfunction "1_1") (pintype "passive"))
      (node (ref "R15") (pin "1") (pinfunction "1_1") (pintype "passive"))
      (node (ref "U6") (pin "9") (pinfunction "VDDA_9") (pintype "power_in"))
    )
    (net (code "237") (name "Net-(U14-{slash}SRCLR)") (class "Default")
      (node (ref "R69") (pin "2") (pinfunction "2_2") (pintype "passive"))
      (node (ref "U14") (pin "10") (pinfunction "/SRCLR_10") (pintype "passive"))
    )
    (net (code "238") (name "Net-(U15-{slash}SRCLR)") (class "Default")
      (node (ref "R67") (pin "2") (pinfunction "2_2") (pintype "passive"))
      (node (ref "U15") (pin "10") (pinfunction "/SRCLR_10") (pintype "passive"))
    )
    (net (code "239") (name "unconnected-(J1-MH1-Pad10)") (class "Default")
      (node (ref "J1") (pin "10") (pinfunction "MH1_10") (pintype "passive"))
    )
    (net (code "240") (name "unconnected-(J1-MH2-Pad11)") (class "Default")
      (node (ref "J1") (pin "11") (pinfunction "MH2_11") (pintype "passive"))
    )
    (net (code "241") (name "unconnected-(J1-Pad2)") (class "Default")
      (node (ref "J1") (pin "2") (pinfunction "2_2") (pintype "passive"))
    )
    (net (code "242") (name "unconnected-(J1-Pad4)") (class "Default")
      (node (ref "J1") (pin "4") (pinfunction "4_4") (pintype "passive"))
    )
    (net (code "243") (name "unconnected-(J1-Pad6)") (class "Default")
      (node (ref "J1") (pin "6") (pinfunction "6_6") (pintype "passive"))
    )
    (net (code "244") (name "unconnected-(S_1_C1-NC1-Pad1)") (class "Default")
      (node (ref "S_1_C1") (pin "1") (pinfunction "NC1_1") (pintype "passive+no_connect"))
    )
    (net (code "245") (name "unconnected-(S_1_C1-NC2-Pad5)") (class "Default")
      (node (ref "S_1_C1") (pin "5") (pinfunction "NC2_5") (pintype "passive+no_connect"))
    )
    (net (code "246") (name "unconnected-(S_1_C1-NC3-Pad9)") (class "Default")
      (node (ref "S_1_C1") (pin "9") (pinfunction "NC3_9") (pintype "passive+no_connect"))
    )
    (net (code "247") (name "unconnected-(S_1_C1-NC4-Pad13)") (class "Default")
      (node (ref "S_1_C1") (pin "13") (pinfunction "NC4_13") (pintype "passive+no_connect"))
    )
    (net (code "248") (name "unconnected-(S_1_C2-NC1-Pad1)") (class "Default")
      (node (ref "S_1_C2") (pin "1") (pinfunction "NC1_1") (pintype "passive+no_connect"))
    )
    (net (code "249") (name "unconnected-(S_1_C2-NC2-Pad5)") (class "Default")
      (node (ref "S_1_C2") (pin "5") (pinfunction "NC2_5") (pintype "passive+no_connect"))
    )
    (net (code "250") (name "unconnected-(S_1_C2-NC3-Pad9)") (class "Default")
      (node (ref "S_1_C2") (pin "9") (pinfunction "NC3_9") (pintype "passive+no_connect"))
    )
    (net (code "251") (name "unconnected-(S_1_C2-NC4-Pad13)") (class "Default")
      (node (ref "S_1_C2") (pin "13") (pinfunction "NC4_13") (pintype "passive+no_connect"))
    )
    (net (code "252") (name "unconnected-(S_1_C3-NC1-Pad1)") (class "Default")
      (node (ref "S_1_C3") (pin "1") (pinfunction "NC1_1") (pintype "passive+no_connect"))
    )
    (net (code "253") (name "unconnected-(S_1_C3-NC2-Pad5)") (class "Default")
      (node (ref "S_1_C3") (pin "5") (pinfunction "NC2_5") (pintype "passive+no_connect"))
    )
    (net (code "254") (name "unconnected-(S_1_C3-NC3-Pad9)") (class "Default")
      (node (ref "S_1_C3") (pin "9") (pinfunction "NC3_9") (pintype "passive+no_connect"))
    )
    (net (code "255") (name "unconnected-(S_1_C3-NC4-Pad13)") (class "Default")
      (node (ref "S_1_C3") (pin "13") (pinfunction "NC4_13") (pintype "passive+no_connect"))
    )
    (net (code "256") (name "unconnected-(S_1_C4-NC1-Pad1)") (class "Default")
      (node (ref "S_1_C4") (pin "1") (pinfunction "NC1_1") (pintype "passive+no_connect"))
    )
    (net (code "257") (name "unconnected-(S_1_C4-NC2-Pad5)") (class "Default")
      (node (ref "S_1_C4") (pin "5") (pinfunction "NC2_5") (pintype "passive+no_connect"))
    )
    (net (code "258") (name "unconnected-(S_1_C4-NC3-Pad9)") (class "Default")
      (node (ref "S_1_C4") (pin "9") (pinfunction "NC3_9") (pintype "passive+no_connect"))
    )
    (net (code "259") (name "unconnected-(S_1_C4-NC4-Pad13)") (class "Default")
      (node (ref "S_1_C4") (pin "13") (pinfunction "NC4_13") (pintype "passive+no_connect"))
    )
    (net (code "260") (name "unconnected-(S_1_C5-NC1-Pad1)") (class "Default")
      (node (ref "S_1_C5") (pin "1") (pinfunction "NC1_1") (pintype "passive+no_connect"))
    )
    (net (code "261") (name "unconnected-(S_1_C5-NC2-Pad5)") (class "Default")
      (node (ref "S_1_C5") (pin "5") (pinfunction "NC2_5") (pintype "passive+no_connect"))
    )
    (net (code "262") (name "unconnected-(S_1_C5-NC3-Pad9)") (class "Default")
      (node (ref "S_1_C5") (pin "9") (pinfunction "NC3_9") (pintype "passive+no_connect"))
    )
    (net (code "263") (name "unconnected-(S_1_C5-NC4-Pad13)") (class "Default")
      (node (ref "S_1_C5") (pin "13") (pinfunction "NC4_13") (pintype "passive+no_connect"))
    )
    (net (code "264") (name "unconnected-(S_1_C6-NC1-Pad1)") (class "Default")
      (node (ref "S_1_C6") (pin "1") (pinfunction "NC1_1") (pintype "passive+no_connect"))
    )
    (net (code "265") (name "unconnected-(S_1_C6-NC2-Pad5)") (class "Default")
      (node (ref "S_1_C6") (pin "5") (pinfunction "NC2_5") (pintype "passive+no_connect"))
    )
    (net (code "266") (name "unconnected-(S_1_C6-NC3-Pad9)") (class "Default")
      (node (ref "S_1_C6") (pin "9") (pinfunction "NC3_9") (pintype "passive+no_connect"))
    )
    (net (code "267") (name "unconnected-(S_1_C6-NC4-Pad13)") (class "Default")
      (node (ref "S_1_C6") (pin "13") (pinfunction "NC4_13") (pintype "passive+no_connect"))
    )
    (net (code "268") (name "unconnected-(S_2_C1-NC1-Pad1)") (class "Default")
      (node (ref "S_2_C1") (pin "1") (pinfunction "NC1_1") (pintype "passive+no_connect"))
    )
    (net (code "269") (name "unconnected-(S_2_C1-NC2-Pad5)") (class "Default")
      (node (ref "S_2_C1") (pin "5") (pinfunction "NC2_5") (pintype "passive+no_connect"))
    )
    (net (code "270") (name "unconnected-(S_2_C1-NC3-Pad9)") (class "Default")
      (node (ref "S_2_C1") (pin "9") (pinfunction "NC3_9") (pintype "passive+no_connect"))
    )
    (net (code "271") (name "unconnected-(S_2_C1-NC4-Pad13)") (class "Default")
      (node (ref "S_2_C1") (pin "13") (pinfunction "NC4_13") (pintype "passive+no_connect"))
    )
    (net (code "272") (name "unconnected-(S_2_C2-NC1-Pad1)") (class "Default")
      (node (ref "S_2_C2") (pin "1") (pinfunction "NC1_1") (pintype "passive+no_connect"))
    )
    (net (code "273") (name "unconnected-(S_2_C2-NC2-Pad5)") (class "Default")
      (node (ref "S_2_C2") (pin "5") (pinfunction "NC2_5") (pintype "passive+no_connect"))
    )
    (net (code "274") (name "unconnected-(S_2_C2-NC3-Pad9)") (class "Default")
      (node (ref "S_2_C2") (pin "9") (pinfunction "NC3_9") (pintype "passive+no_connect"))
    )
    (net (code "275") (name "unconnected-(S_2_C2-NC4-Pad13)") (class "Default")
      (node (ref "S_2_C2") (pin "13") (pinfunction "NC4_13") (pintype "passive+no_connect"))
    )
    (net (code "276") (name "unconnected-(S_2_C3-NC1-Pad1)") (class "Default")
      (node (ref "S_2_C3") (pin "1") (pinfunction "NC1_1") (pintype "passive+no_connect"))
    )
    (net (code "277") (name "unconnected-(S_2_C3-NC2-Pad5)") (class "Default")
      (node (ref "S_2_C3") (pin "5") (pinfunction "NC2_5") (pintype "passive+no_connect"))
    )
    (net (code "278") (name "unconnected-(S_2_C3-NC3-Pad9)") (class "Default")
      (node (ref "S_2_C3") (pin "9") (pinfunction "NC3_9") (pintype "passive+no_connect"))
    )
    (net (code "279") (name "unconnected-(S_2_C3-NC4-Pad13)") (class "Default")
      (node (ref "S_2_C3") (pin "13") (pinfunction "NC4_13") (pintype "passive+no_connect"))
    )
    (net (code "280") (name "unconnected-(S_2_C4-NC1-Pad1)") (class "Default")
      (node (ref "S_2_C4") (pin "1") (pinfunction "NC1_1") (pintype "passive+no_connect"))
    )
    (net (code "281") (name "unconnected-(S_2_C4-NC2-Pad5)") (class "Default")
      (node (ref "S_2_C4") (pin "5") (pinfunction "NC2_5") (pintype "passive+no_connect"))
    )
    (net (code "282") (name "unconnected-(S_2_C4-NC3-Pad9)") (class "Default")
      (node (ref "S_2_C4") (pin "9") (pinfunction "NC3_9") (pintype "passive+no_connect"))
    )
    (net (code "283") (name "unconnected-(S_2_C4-NC4-Pad13)") (class "Default")
      (node (ref "S_2_C4") (pin "13") (pinfunction "NC4_13") (pintype "passive+no_connect"))
    )
    (net (code "284") (name "unconnected-(S_2_C5-NC1-Pad1)") (class "Default")
      (node (ref "S_2_C5") (pin "1") (pinfunction "NC1_1") (pintype "passive+no_connect"))
    )
    (net (code "285") (name "unconnected-(S_2_C5-NC2-Pad5)") (class "Default")
      (node (ref "S_2_C5") (pin "5") (pinfunction "NC2_5") (pintype "passive+no_connect"))
    )
    (net (code "286") (name "unconnected-(S_2_C5-NC3-Pad9)") (class "Default")
      (node (ref "S_2_C5") (pin "9") (pinfunction "NC3_9") (pintype "passive+no_connect"))
    )
    (net (code "287") (name "unconnected-(S_2_C5-NC4-Pad13)") (class "Default")
      (node (ref "S_2_C5") (pin "13") (pinfunction "NC4_13") (pintype "passive+no_connect"))
    )
    (net (code "288") (name "unconnected-(S_2_C6-NC1-Pad1)") (class "Default")
      (node (ref "S_2_C6") (pin "1") (pinfunction "NC1_1") (pintype "passive+no_connect"))
    )
    (net (code "289") (name "unconnected-(S_2_C6-NC2-Pad5)") (class "Default")
      (node (ref "S_2_C6") (pin "5") (pinfunction "NC2_5") (pintype "passive+no_connect"))
    )
    (net (code "290") (name "unconnected-(S_2_C6-NC3-Pad9)") (class "Default")
      (node (ref "S_2_C6") (pin "9") (pinfunction "NC3_9") (pintype "passive+no_connect"))
    )
    (net (code "291") (name "unconnected-(S_2_C6-NC4-Pad13)") (class "Default")
      (node (ref "S_2_C6") (pin "13") (pinfunction "NC4_13") (pintype "passive+no_connect"))
    )
    (net (code "292") (name "unconnected-(S_3_C1-NC1-Pad1)") (class "Default")
      (node (ref "S_3_C1") (pin "1") (pinfunction "NC1_1") (pintype "passive+no_connect"))
    )
    (net (code "293") (name "unconnected-(S_3_C1-NC2-Pad5)") (class "Default")
      (node (ref "S_3_C1") (pin "5") (pinfunction "NC2_5") (pintype "passive+no_connect"))
    )
    (net (code "294") (name "unconnected-(S_3_C1-NC3-Pad9)") (class "Default")
      (node (ref "S_3_C1") (pin "9") (pinfunction "NC3_9") (pintype "passive+no_connect"))
    )
    (net (code "295") (name "unconnected-(S_3_C1-NC4-Pad13)") (class "Default")
      (node (ref "S_3_C1") (pin "13") (pinfunction "NC4_13") (pintype "passive+no_connect"))
    )
    (net (code "296") (name "unconnected-(S_3_C2-NC1-Pad1)") (class "Default")
      (node (ref "S_3_C2") (pin "1") (pinfunction "NC1_1") (pintype "passive+no_connect"))
    )
    (net (code "297") (name "unconnected-(S_3_C2-NC2-Pad5)") (class "Default")
      (node (ref "S_3_C2") (pin "5") (pinfunction "NC2_5") (pintype "passive+no_connect"))
    )
    (net (code "298") (name "unconnected-(S_3_C2-NC3-Pad9)") (class "Default")
      (node (ref "S_3_C2") (pin "9") (pinfunction "NC3_9") (pintype "passive+no_connect"))
    )
    (net (code "299") (name "unconnected-(S_3_C2-NC4-Pad13)") (class "Default")
      (node (ref "S_3_C2") (pin "13") (pinfunction "NC4_13") (pintype "passive+no_connect"))
    )
    (net (code "300") (name "unconnected-(S_3_C3-NC1-Pad1)") (class "Default")
      (node (ref "S_3_C3") (pin "1") (pinfunction "NC1_1") (pintype "passive+no_connect"))
    )
    (net (code "301") (name "unconnected-(S_3_C3-NC2-Pad5)") (class "Default")
      (node (ref "S_3_C3") (pin "5") (pinfunction "NC2_5") (pintype "passive+no_connect"))
    )
    (net (code "302") (name "unconnected-(S_3_C3-NC3-Pad9)") (class "Default")
      (node (ref "S_3_C3") (pin "9") (pinfunction "NC3_9") (pintype "passive+no_connect"))
    )
    (net (code "303") (name "unconnected-(S_3_C3-NC4-Pad13)") (class "Default")
      (node (ref "S_3_C3") (pin "13") (pinfunction "NC4_13") (pintype "passive+no_connect"))
    )
    (net (code "304") (name "unconnected-(S_3_C4-NC1-Pad1)") (class "Default")
      (node (ref "S_3_C4") (pin "1") (pinfunction "NC1_1") (pintype "passive+no_connect"))
    )
    (net (code "305") (name "unconnected-(S_3_C4-NC2-Pad5)") (class "Default")
      (node (ref "S_3_C4") (pin "5") (pinfunction "NC2_5") (pintype "passive+no_connect"))
    )
    (net (code "306") (name "unconnected-(S_3_C4-NC3-Pad9)") (class "Default")
      (node (ref "S_3_C4") (pin "9") (pinfunction "NC3_9") (pintype "passive+no_connect"))
    )
    (net (code "307") (name "unconnected-(S_3_C4-NC4-Pad13)") (class "Default")
      (node (ref "S_3_C4") (pin "13") (pinfunction "NC4_13") (pintype "passive+no_connect"))
    )
    (net (code "308") (name "unconnected-(S_3_C5-NC1-Pad1)") (class "Default")
      (node (ref "S_3_C5") (pin "1") (pinfunction "NC1_1") (pintype "passive+no_connect"))
    )
    (net (code "309") (name "unconnected-(S_3_C5-NC2-Pad5)") (class "Default")
      (node (ref "S_3_C5") (pin "5") (pinfunction "NC2_5") (pintype "passive+no_connect"))
    )
    (net (code "310") (name "unconnected-(S_3_C5-NC3-Pad9)") (class "Default")
      (node (ref "S_3_C5") (pin "9") (pinfunction "NC3_9") (pintype "passive+no_connect"))
    )
    (net (code "311") (name "unconnected-(S_3_C5-NC4-Pad13)") (class "Default")
      (node (ref "S_3_C5") (pin "13") (pinfunction "NC4_13") (pintype "passive+no_connect"))
    )
    (net (code "312") (name "unconnected-(S_3_C6-NC1-Pad1)") (class "Default")
      (node (ref "S_3_C6") (pin "1") (pinfunction "NC1_1") (pintype "passive+no_connect"))
    )
    (net (code "313") (name "unconnected-(S_3_C6-NC2-Pad5)") (class "Default")
      (node (ref "S_3_C6") (pin "5") (pinfunction "NC2_5") (pintype "passive+no_connect"))
    )
    (net (code "314") (name "unconnected-(S_3_C6-NC3-Pad9)") (class "Default")
      (node (ref "S_3_C6") (pin "9") (pinfunction "NC3_9") (pintype "passive+no_connect"))
    )
    (net (code "315") (name "unconnected-(S_3_C6-NC4-Pad13)") (class "Default")
      (node (ref "S_3_C6") (pin "13") (pinfunction "NC4_13") (pintype "passive+no_connect"))
    )
    (net (code "316") (name "unconnected-(S_4_C1-NC1-Pad1)") (class "Default")
      (node (ref "S_4_C1") (pin "1") (pinfunction "NC1_1") (pintype "passive+no_connect"))
    )
    (net (code "317") (name "unconnected-(S_4_C1-NC2-Pad5)") (class "Default")
      (node (ref "S_4_C1") (pin "5") (pinfunction "NC2_5") (pintype "passive+no_connect"))
    )
    (net (code "318") (name "unconnected-(S_4_C1-NC3-Pad9)") (class "Default")
      (node (ref "S_4_C1") (pin "9") (pinfunction "NC3_9") (pintype "passive+no_connect"))
    )
    (net (code "319") (name "unconnected-(S_4_C1-NC4-Pad13)") (class "Default")
      (node (ref "S_4_C1") (pin "13") (pinfunction "NC4_13") (pintype "passive+no_connect"))
    )
    (net (code "320") (name "unconnected-(S_4_C2-NC1-Pad1)") (class "Default")
      (node (ref "S_4_C2") (pin "1") (pinfunction "NC1_1") (pintype "passive+no_connect"))
    )
    (net (code "321") (name "unconnected-(S_4_C2-NC2-Pad5)") (class "Default")
      (node (ref "S_4_C2") (pin "5") (pinfunction "NC2_5") (pintype "passive+no_connect"))
    )
    (net (code "322") (name "unconnected-(S_4_C2-NC3-Pad9)") (class "Default")
      (node (ref "S_4_C2") (pin "9") (pinfunction "NC3_9") (pintype "passive+no_connect"))
    )
    (net (code "323") (name "unconnected-(S_4_C2-NC4-Pad13)") (class "Default")
      (node (ref "S_4_C2") (pin "13") (pinfunction "NC4_13") (pintype "passive+no_connect"))
    )
    (net (code "324") (name "unconnected-(S_4_C3-NC1-Pad1)") (class "Default")
      (node (ref "S_4_C3") (pin "1") (pinfunction "NC1_1") (pintype "passive+no_connect"))
    )
    (net (code "325") (name "unconnected-(S_4_C3-NC2-Pad5)") (class "Default")
      (node (ref "S_4_C3") (pin "5") (pinfunction "NC2_5") (pintype "passive+no_connect"))
    )
    (net (code "326") (name "unconnected-(S_4_C3-NC3-Pad9)") (class "Default")
      (node (ref "S_4_C3") (pin "9") (pinfunction "NC3_9") (pintype "passive+no_connect"))
    )
    (net (code "327") (name "unconnected-(S_4_C3-NC4-Pad13)") (class "Default")
      (node (ref "S_4_C3") (pin "13") (pinfunction "NC4_13") (pintype "passive+no_connect"))
    )
    (net (code "328") (name "unconnected-(S_4_C4-NC1-Pad1)") (class "Default")
      (node (ref "S_4_C4") (pin "1") (pinfunction "NC1_1") (pintype "passive+no_connect"))
    )
    (net (code "329") (name "unconnected-(S_4_C4-NC2-Pad5)") (class "Default")
      (node (ref "S_4_C4") (pin "5") (pinfunction "NC2_5") (pintype "passive+no_connect"))
    )
    (net (code "330") (name "unconnected-(S_4_C4-NC3-Pad9)") (class "Default")
      (node (ref "S_4_C4") (pin "9") (pinfunction "NC3_9") (pintype "passive+no_connect"))
    )
    (net (code "331") (name "unconnected-(S_4_C4-NC4-Pad13)") (class "Default")
      (node (ref "S_4_C4") (pin "13") (pinfunction "NC4_13") (pintype "passive+no_connect"))
    )
    (net (code "332") (name "unconnected-(S_4_C5-NC1-Pad1)") (class "Default")
      (node (ref "S_4_C5") (pin "1") (pinfunction "NC1_1") (pintype "passive+no_connect"))
    )
    (net (code "333") (name "unconnected-(S_4_C5-NC2-Pad5)") (class "Default")
      (node (ref "S_4_C5") (pin "5") (pinfunction "NC2_5") (pintype "passive+no_connect"))
    )
    (net (code "334") (name "unconnected-(S_4_C5-NC3-Pad9)") (class "Default")
      (node (ref "S_4_C5") (pin "9") (pinfunction "NC3_9") (pintype "passive+no_connect"))
    )
    (net (code "335") (name "unconnected-(S_4_C5-NC4-Pad13)") (class "Default")
      (node (ref "S_4_C5") (pin "13") (pinfunction "NC4_13") (pintype "passive+no_connect"))
    )
    (net (code "336") (name "unconnected-(S_4_C6-NC1-Pad1)") (class "Default")
      (node (ref "S_4_C6") (pin "1") (pinfunction "NC1_1") (pintype "passive+no_connect"))
    )
    (net (code "337") (name "unconnected-(S_4_C6-NC2-Pad5)") (class "Default")
      (node (ref "S_4_C6") (pin "5") (pinfunction "NC2_5") (pintype "passive+no_connect"))
    )
    (net (code "338") (name "unconnected-(S_4_C6-NC3-Pad9)") (class "Default")
      (node (ref "S_4_C6") (pin "9") (pinfunction "NC3_9") (pintype "passive+no_connect"))
    )
    (net (code "339") (name "unconnected-(S_4_C6-NC4-Pad13)") (class "Default")
      (node (ref "S_4_C6") (pin "13") (pinfunction "NC4_13") (pintype "passive+no_connect"))
    )
    (net (code "340") (name "unconnected-(U6-PA0-WKUP-Pad10)") (class "Default")
      (node (ref "U6") (pin "10") (pinfunction "PA0-WKUP_10") (pintype "bidirectional"))
    )
    (net (code "341") (name "unconnected-(U6-PA1-Pad11)") (class "Default")
      (node (ref "U6") (pin "11") (pinfunction "PA1_11") (pintype "bidirectional"))
    )
    (net (code "342") (name "unconnected-(U6-PA4-Pad14)") (class "Default")
      (node (ref "U6") (pin "14") (pinfunction "PA4_14") (pintype "bidirectional"))
    )
    (net (code "343") (name "unconnected-(U6-PA5-Pad15)") (class "Default")
      (node (ref "U6") (pin "15") (pinfunction "PA5_15") (pintype "bidirectional"))
    )
    (net (code "344") (name "unconnected-(U6-PA6-Pad16)") (class "Default")
      (node (ref "U6") (pin "16") (pinfunction "PA6_16") (pintype "bidirectional"))
    )
    (net (code "345") (name "unconnected-(U6-PA12-Pad33)") (class "Default")
      (node (ref "U6") (pin "33") (pinfunction "PA12_33") (pintype "bidirectional"))
    )
    (net (code "346") (name "unconnected-(U6-PA15{slash}JTDI-Pad38)") (class "Default")
      (node (ref "U6") (pin "38") (pinfunction "PA15/JTDI_38") (pintype "bidirectional"))
    )
    (net (code "347") (name "unconnected-(U6-PB0-Pad18)") (class "Default")
      (node (ref "U6") (pin "18") (pinfunction "PB0_18") (pintype "bidirectional"))
    )
    (net (code "348") (name "unconnected-(U6-PB1-Pad19)") (class "Default")
      (node (ref "U6") (pin "19") (pinfunction "PB1_19") (pintype "bidirectional"))
    )
    (net (code "349") (name "unconnected-(U6-PB3{slash}JTDO-Pad39)") (class "Default")
      (node (ref "U6") (pin "39") (pinfunction "PB3/JTDO_39") (pintype "bidirectional"))
    )
    (net (code "350") (name "unconnected-(U6-PB4{slash}JNTRST-Pad40)") (class "Default")
      (node (ref "U6") (pin "40") (pinfunction "PB4/JNTRST_40") (pintype "bidirectional"))
    )
    (net (code "351") (name "unconnected-(U6-PB5-Pad41)") (class "Default")
      (node (ref "U6") (pin "41") (pinfunction "PB5_41") (pintype "bidirectional"))
    )
    (net (code "352") (name "unconnected-(U6-PB12-Pad25)") (class "Default")
      (node (ref "U6") (pin "25") (pinfunction "PB12_25") (pintype "bidirectional"))
    )
    (net (code "353") (name "unconnected-(U6-PB13-Pad26)") (class "Default")
      (node (ref "U6") (pin "26") (pinfunction "PB13_26") (pintype "bidirectional"))
    )
    (net (code "354") (name "unconnected-(U6-PC13-TAMPER-RTC-Pad2)") (class "Default")
      (node (ref "U6") (pin "2") (pinfunction "PC13-TAMPER-RTC_2") (pintype "bidirectional"))
    )
    (net (code "355") (name "unconnected-(U15-QH'-Pad9)") (class "Default")
      (node (ref "U15") (pin "9") (pinfunction "QH'_9") (pintype "passive+no_connect"))
    )
    (net (code "356") (name "unconnected-(Y1-GROUND-Pad2)") (class "Default")
      (node (ref "Y1") (pin "2") (pinfunction "GROUND_2") (pintype "passive"))
    )
    (net (code "357") (name "unconnected-(Y1-GROUND-Pad4)") (class "Default")
      (node (ref "Y1") (pin "4") (pinfunction "GROUND_4") (pintype "passive"))
    )
  )
)
